# led-matrix-cape.net
KiCad netlist of a schematic drawn in EAGLE
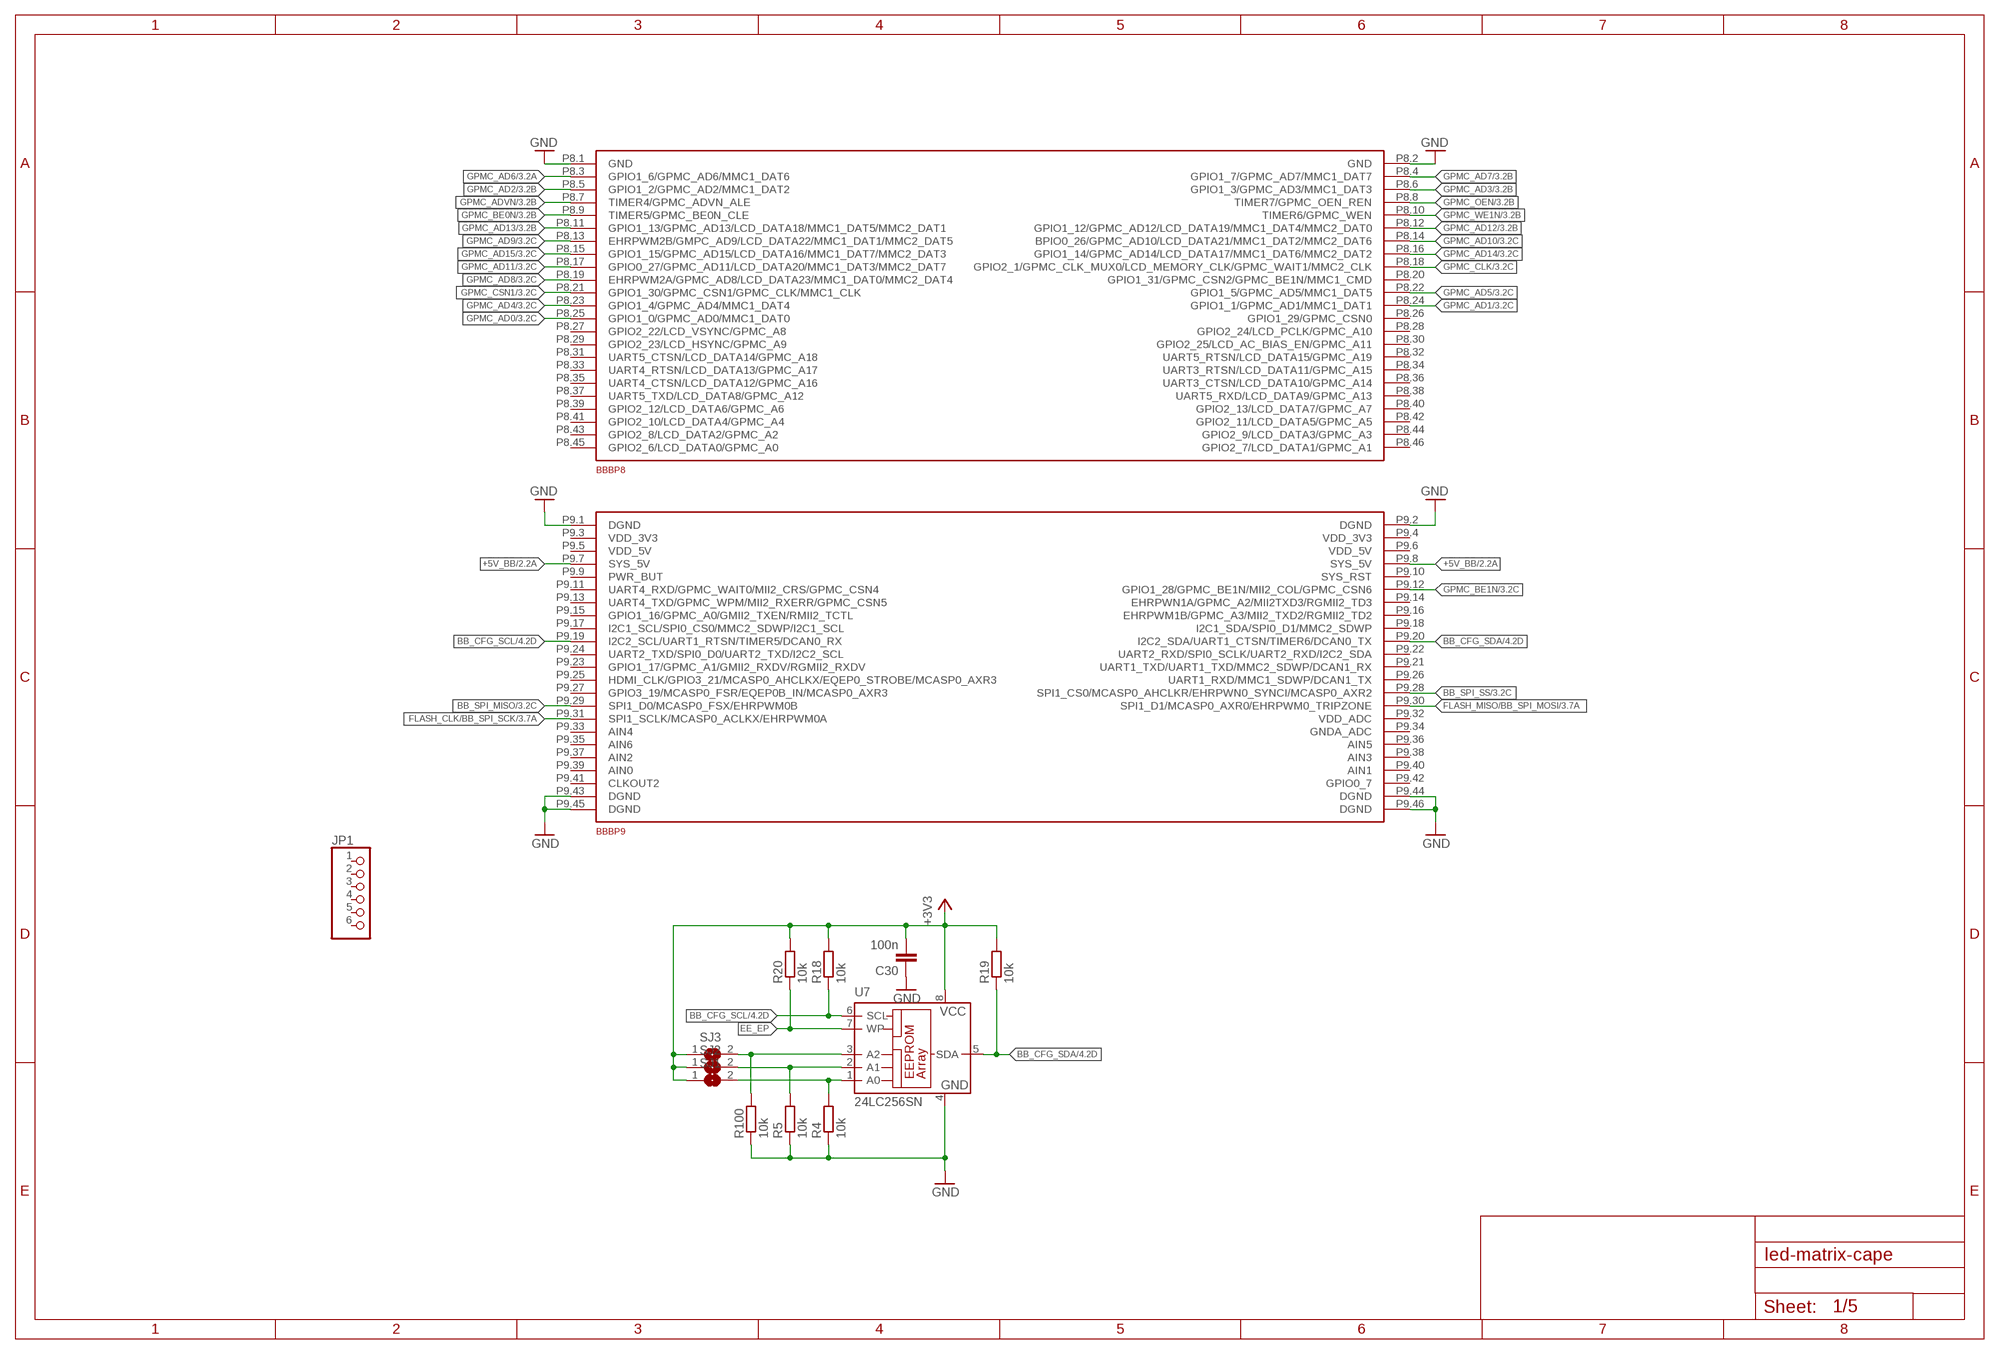
[diagram p0: schematic, sheet 1]
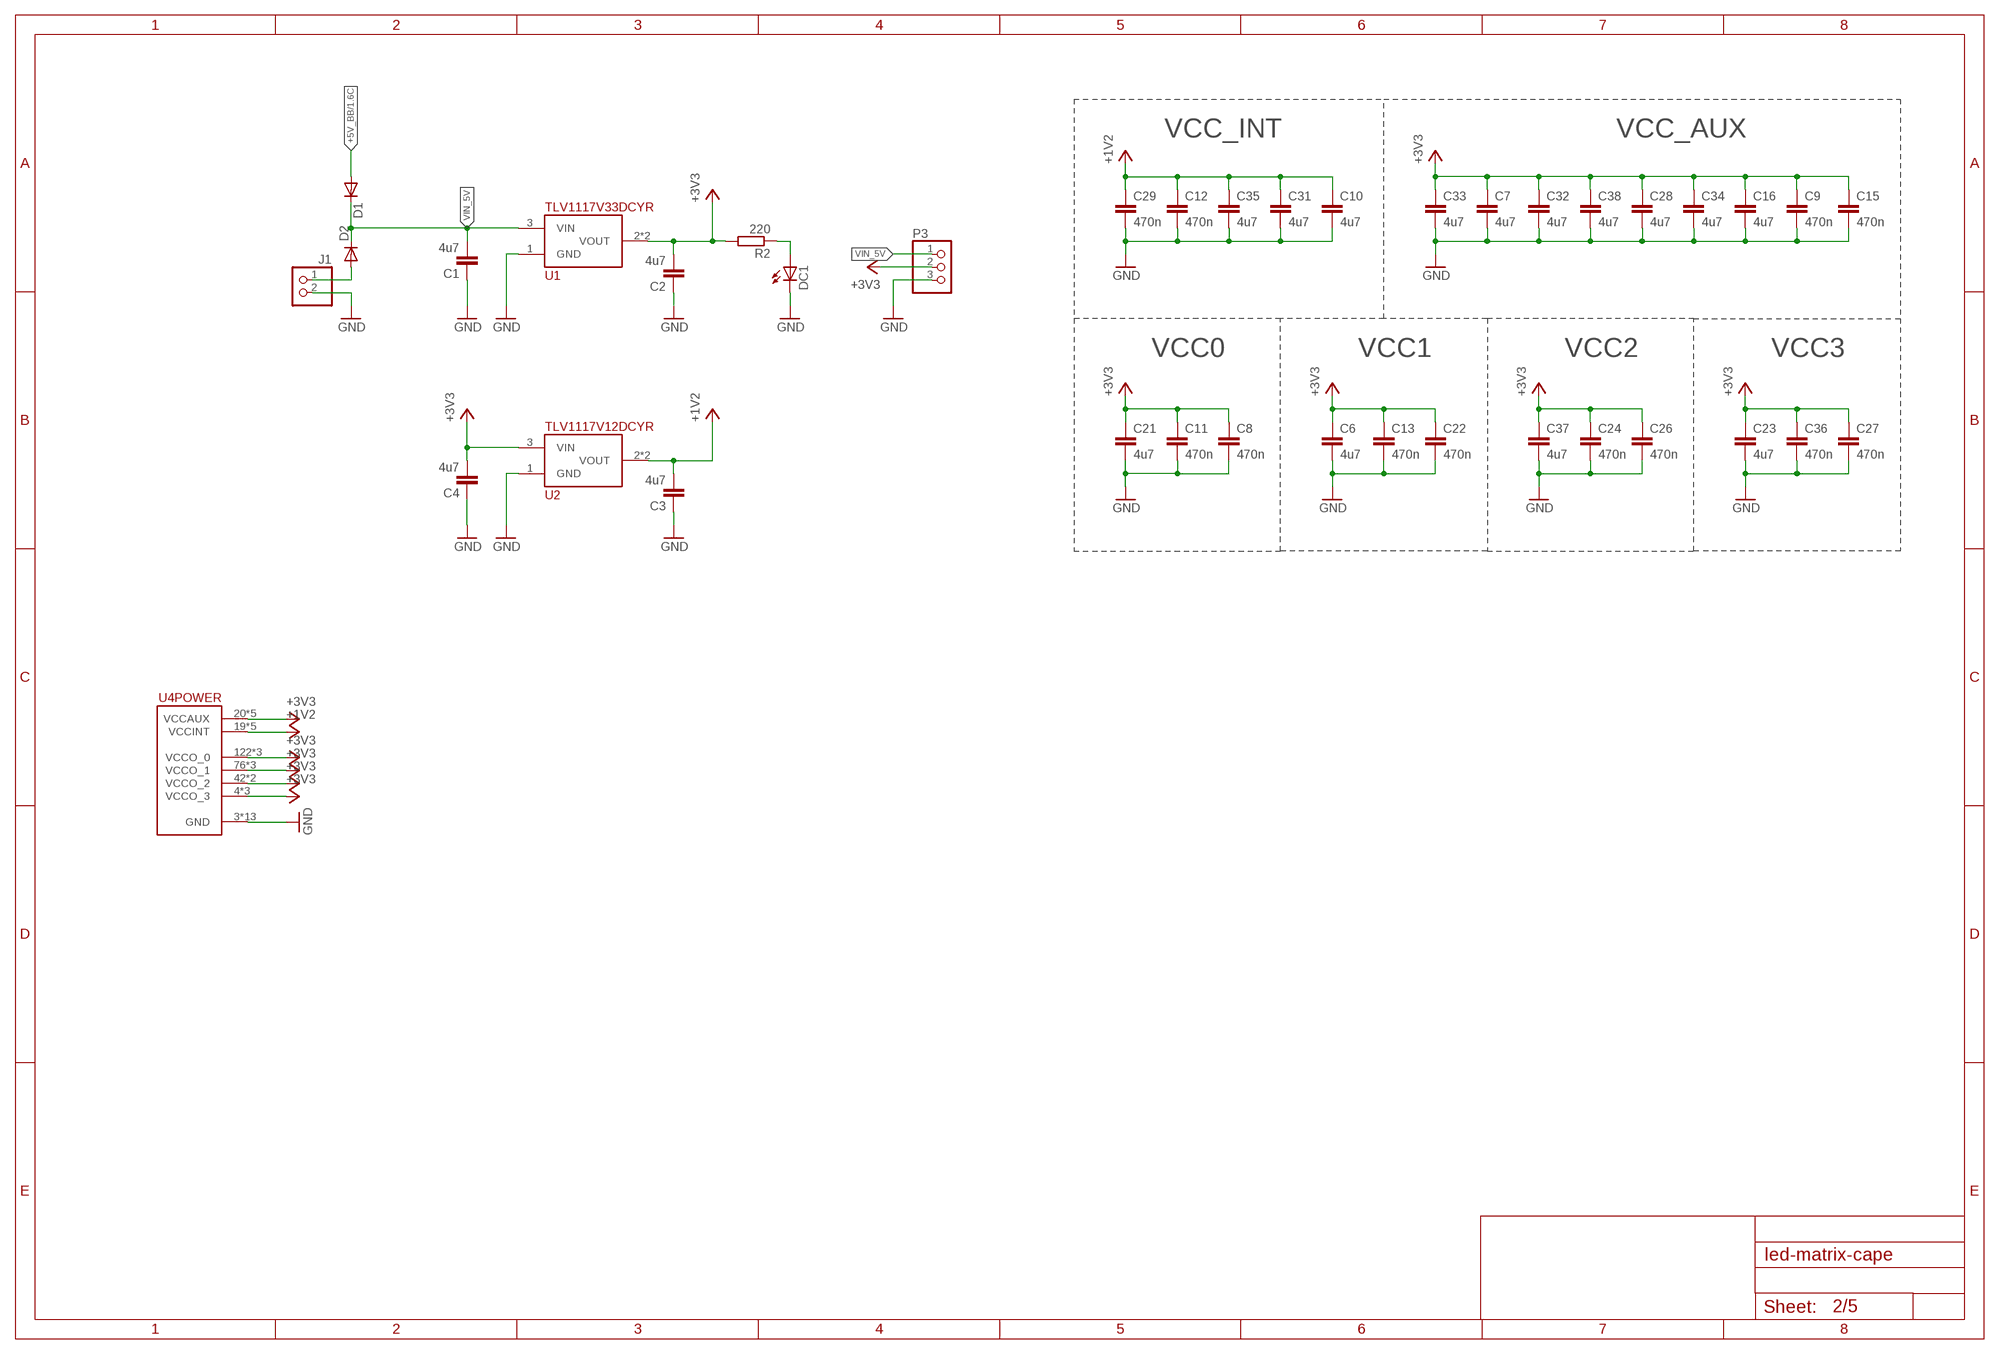
[diagram p1: schematic, sheet 2]
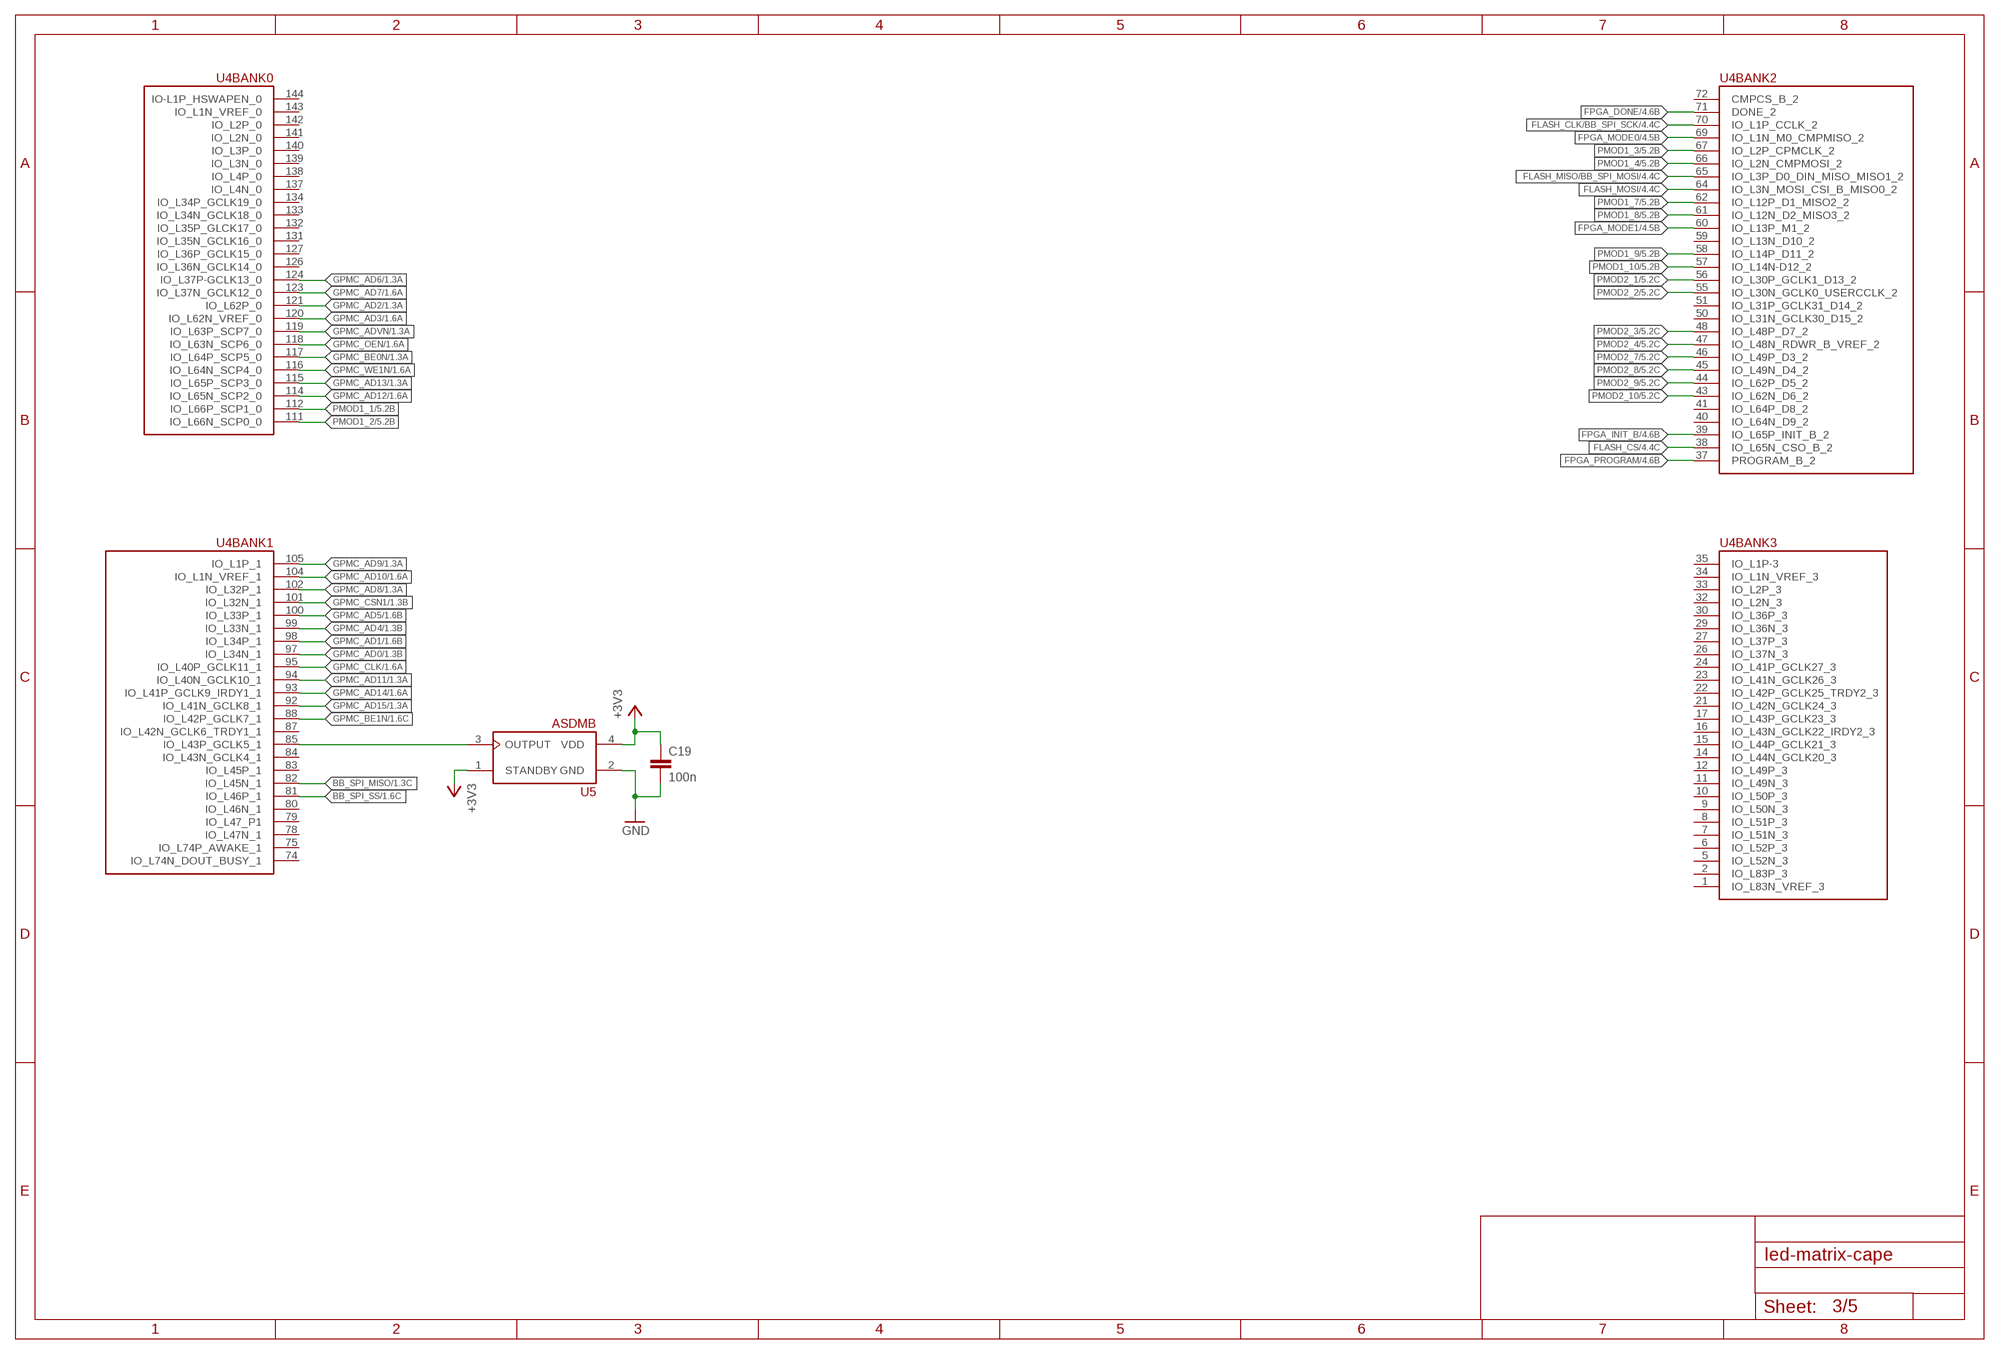
[diagram p2: schematic, sheet 3]
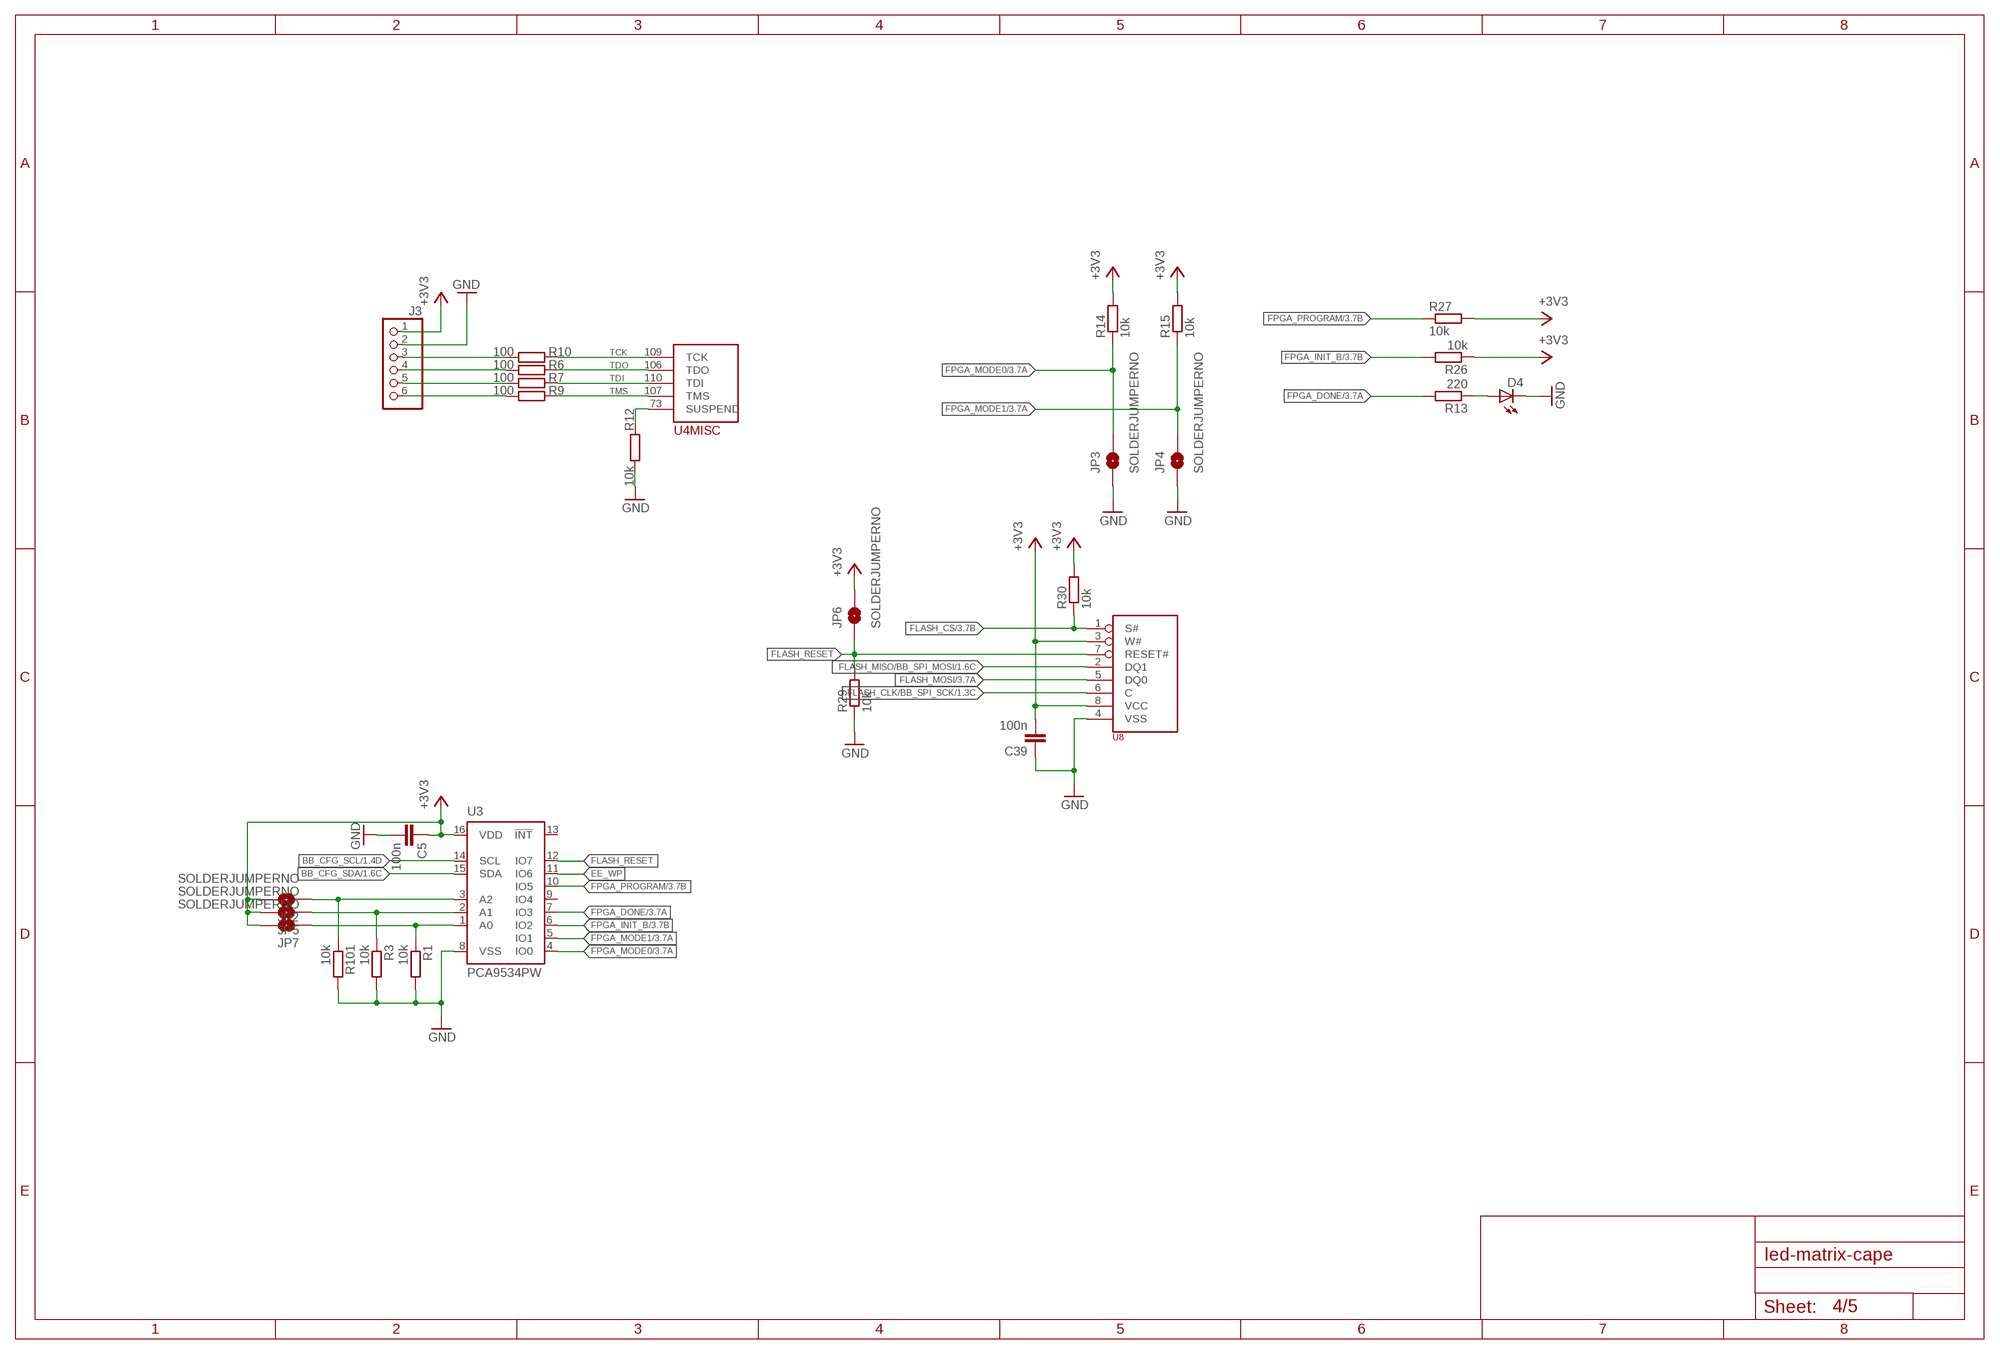
[diagram p3: schematic, sheet 4]
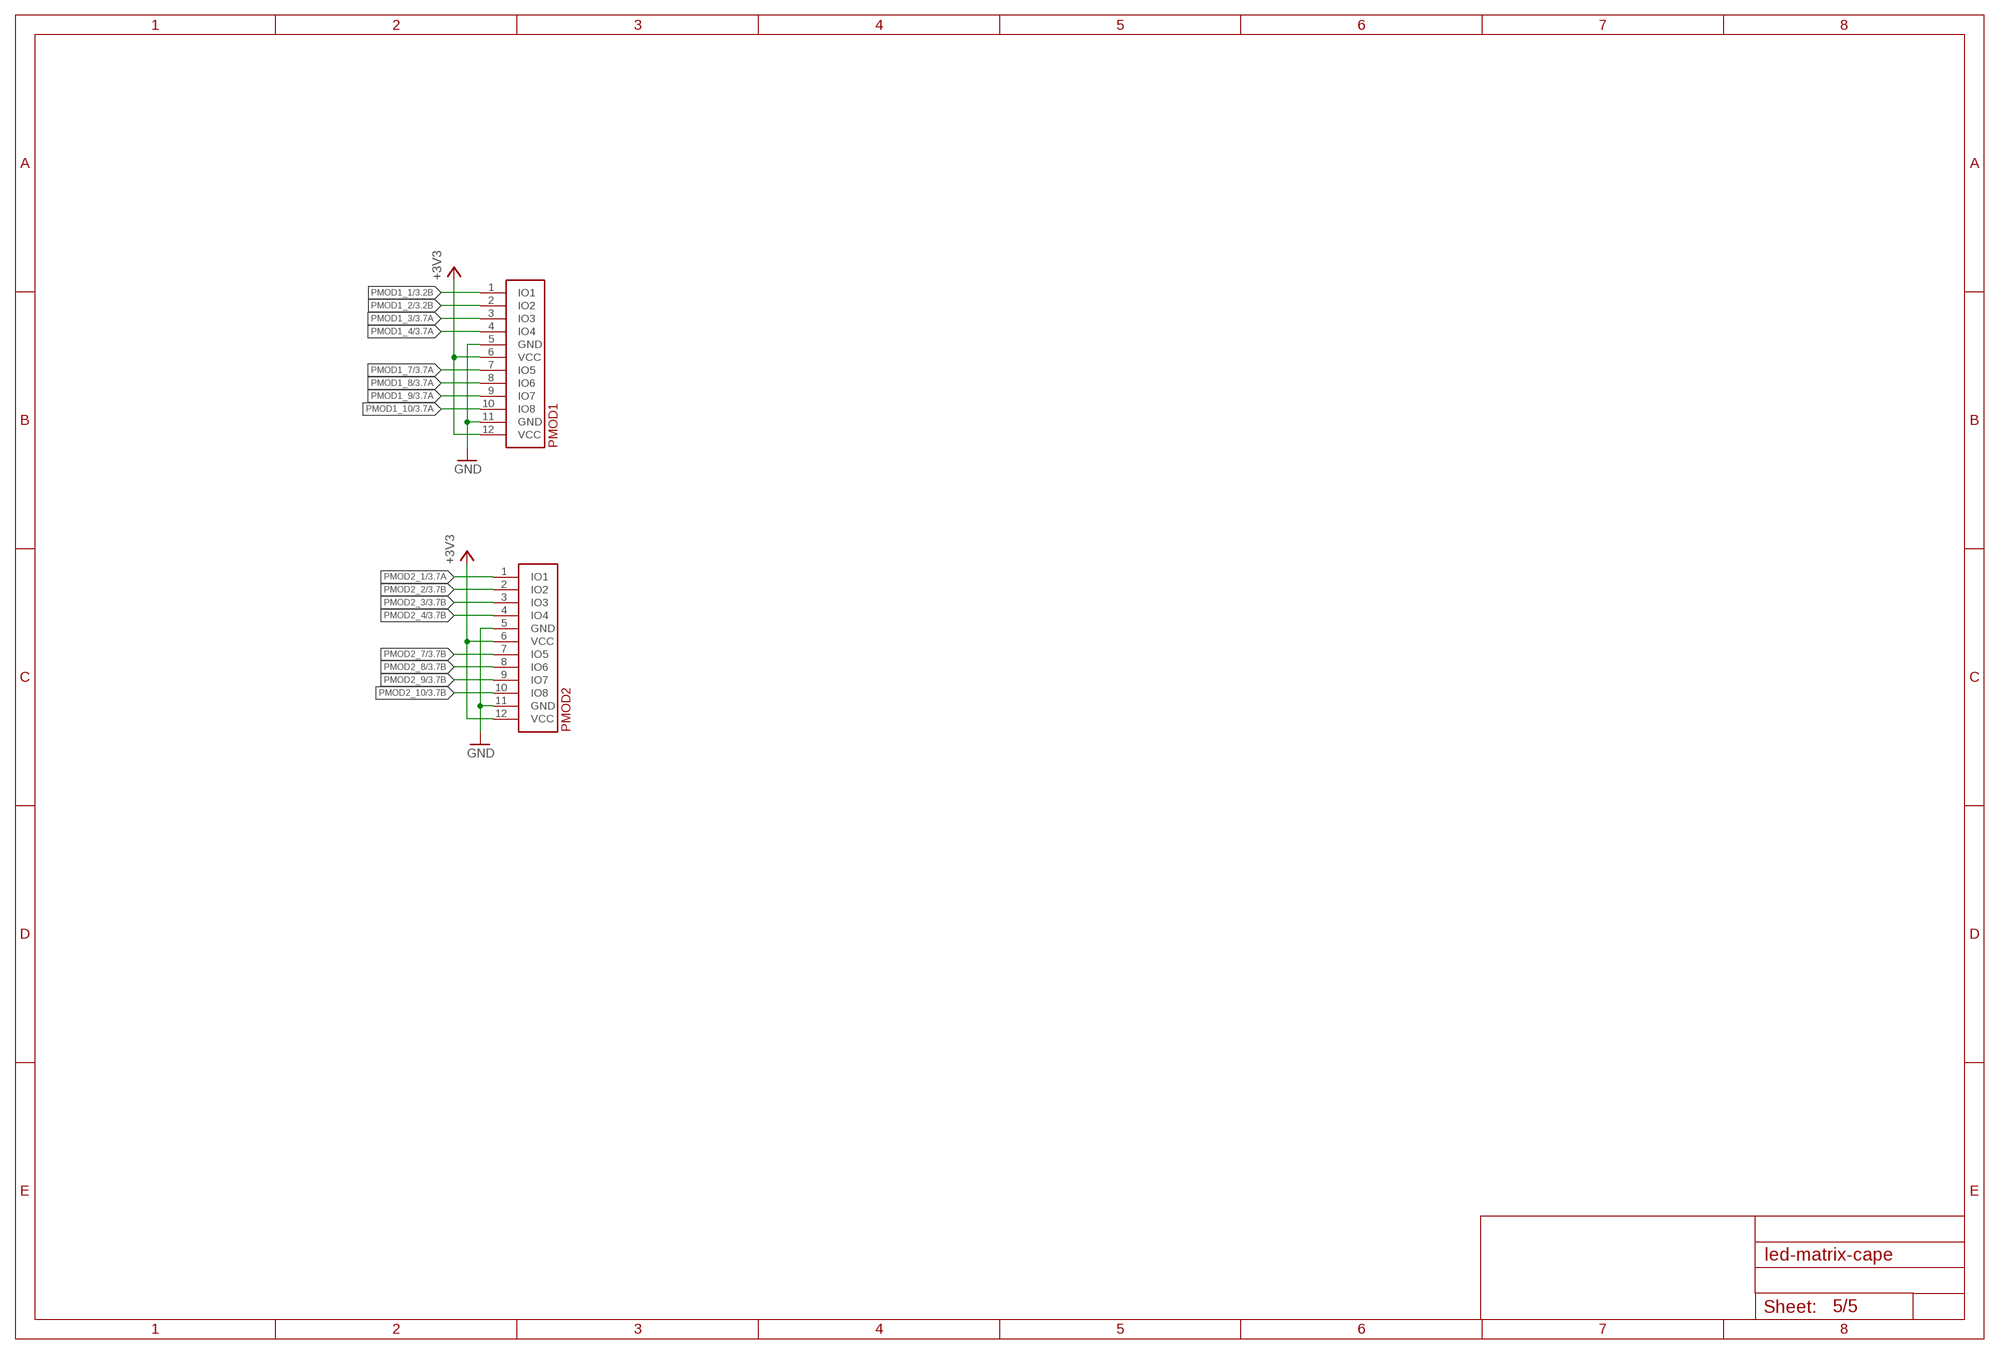
[diagram p4: schematic, sheet 5]

(export (version "E")
  (design (tool "Eeschema 10.0.6"))
  (components
    (comp (ref "C1")
      (value "4u7")
      (footprint "eagle-import:C0603")
      (libsource (lib "eagle-import") (part "C-EUC0603"))
    )
    (comp (ref "C2")
      (value "4u7")
      (footprint "eagle-import:C0603")
      (libsource (lib "eagle-import") (part "C-EUC0603"))
    )
    (comp (ref "C3")
      (value "4u7")
      (footprint "eagle-import:C0603")
      (libsource (lib "eagle-import") (part "C-EUC0603"))
    )
    (comp (ref "C4")
      (value "4u7")
      (footprint "eagle-import:C0603")
      (libsource (lib "eagle-import") (part "C-EUC0603"))
    )
    (comp (ref "C6")
      (value "4u7")
      (footprint "eagle-import:C0603")
      (libsource (lib "eagle-import") (part "C-EUC0603"))
    )
    (comp (ref "C7")
      (value "4u7")
      (footprint "eagle-import:C0603")
      (libsource (lib "eagle-import") (part "C-EUC0603"))
    )
    (comp (ref "C8")
      (value "470n")
      (footprint "eagle-import:C0603")
      (libsource (lib "eagle-import") (part "C-EUC0603"))
    )
    (comp (ref "C9")
      (value "470n")
      (footprint "eagle-import:C0603")
      (libsource (lib "eagle-import") (part "C-EUC0603"))
    )
    (comp (ref "C10")
      (value "4u7")
      (footprint "eagle-import:C0603")
      (libsource (lib "eagle-import") (part "C-EUC0603"))
    )
    (comp (ref "C11")
      (value "470n")
      (footprint "eagle-import:C0603")
      (libsource (lib "eagle-import") (part "C-EUC0603"))
    )
    (comp (ref "C12")
      (value "470n")
      (footprint "eagle-import:C0603")
      (libsource (lib "eagle-import") (part "C-EUC0603"))
    )
    (comp (ref "C13")
      (value "470n")
      (footprint "eagle-import:C0603")
      (libsource (lib "eagle-import") (part "C-EUC0603"))
    )
    (comp (ref "C15")
      (value "470n")
      (footprint "eagle-import:C0603")
      (libsource (lib "eagle-import") (part "C-EUC0603"))
    )
    (comp (ref "C16")
      (value "4u7")
      (footprint "eagle-import:C0603")
      (libsource (lib "eagle-import") (part "C-EUC0603"))
    )
    (comp (ref "C21")
      (value "4u7")
      (footprint "eagle-import:C0603")
      (libsource (lib "eagle-import") (part "C-EUC0603"))
    )
    (comp (ref "C22")
      (value "470n")
      (footprint "eagle-import:C0603")
      (libsource (lib "eagle-import") (part "C-EUC0603"))
    )
    (comp (ref "C23")
      (value "4u7")
      (footprint "eagle-import:C0603")
      (libsource (lib "eagle-import") (part "C-EUC0603"))
    )
    (comp (ref "C24")
      (value "470n")
      (footprint "eagle-import:C0603")
      (libsource (lib "eagle-import") (part "C-EUC0603"))
    )
    (comp (ref "C26")
      (value "470n")
      (footprint "eagle-import:C0603")
      (libsource (lib "eagle-import") (part "C-EUC0603"))
    )
    (comp (ref "C27")
      (value "470n")
      (footprint "eagle-import:C0603")
      (libsource (lib "eagle-import") (part "C-EUC0603"))
    )
    (comp (ref "C28")
      (value "4u7")
      (footprint "eagle-import:C0603")
      (libsource (lib "eagle-import") (part "C-EUC0603"))
    )
    (comp (ref "C29")
      (value "470n")
      (footprint "eagle-import:C0603")
      (libsource (lib "eagle-import") (part "C-EUC0603"))
    )
    (comp (ref "C31")
      (value "4u7")
      (footprint "eagle-import:C0603")
      (libsource (lib "eagle-import") (part "C-EUC0603"))
    )
    (comp (ref "C32")
      (value "4u7")
      (footprint "eagle-import:C0603")
      (libsource (lib "eagle-import") (part "C-EUC0603"))
    )
    (comp (ref "C33")
      (value "4u7")
      (footprint "eagle-import:C0603")
      (libsource (lib "eagle-import") (part "C-EUC0603"))
    )
    (comp (ref "C34")
      (value "4u7")
      (footprint "eagle-import:C0603")
      (libsource (lib "eagle-import") (part "C-EUC0603"))
    )
    (comp (ref "C35")
      (value "4u7")
      (footprint "eagle-import:C0603")
      (libsource (lib "eagle-import") (part "C-EUC0603"))
    )
    (comp (ref "C36")
      (value "470n")
      (footprint "eagle-import:C0603")
      (libsource (lib "eagle-import") (part "C-EUC0603"))
    )
    (comp (ref "C37")
      (value "4u7")
      (footprint "eagle-import:C0603")
      (libsource (lib "eagle-import") (part "C-EUC0603"))
    )
    (comp (ref "C38")
      (value "4u7")
      (footprint "eagle-import:C0603")
      (libsource (lib "eagle-import") (part "C-EUC0603"))
    )
    (comp (ref "D1")
      (value "DIODE-SOD123")
      (footprint "eagle-import:SOD123")
      (libsource (lib "eagle-import") (part "DIODE-SOD123"))
    )
    (comp (ref "D2")
      (value "DIODE-SOD123")
      (footprint "eagle-import:SOD123")
      (libsource (lib "eagle-import") (part "DIODE-SOD123"))
    )
    (comp (ref "DC1")
      (value "LEDCHIP-LED0805")
      (footprint "eagle-import:CHIP-LED0805")
      (libsource (lib "eagle-import") (part "LEDCHIP-LED0805"))
    )
    (comp (ref "J1")
      (value "PINHD-1X2")
      (footprint "eagle-import:1X02")
      (libsource (lib "eagle-import") (part "PINHD-1X2"))
    )
    (comp (ref "P3")
      (value "PINHD-1X3")
      (footprint "eagle-import:1X03")
      (libsource (lib "eagle-import") (part "PINHD-1X3"))
    )
    (comp (ref "R2")
      (value "220")
      (footprint "eagle-import:R0805")
      (libsource (lib "eagle-import") (part "R-EU_R0805"))
    )
    (comp (ref "U1")
      (value "TLV1117V33DCYR")
      (footprint "eagle-import:SOT223")
      (libsource (lib "eagle-import") (part "TLV1117V"))
    )
    (comp (ref "U2")
      (value "TLV1117V12DCYR")
      (footprint "eagle-import:SOT223")
      (libsource (lib "eagle-import") (part "TLV1117V"))
    )
    (comp (ref "U4")
      (value "XC6SLX9-2TQG144C")
      (footprint "eagle-import:TQFP144")
      (libsource (lib "eagle-import") (part "XC6SLX9-2TQG144C"))
    )
    (comp (ref "C5")
      (value "100n")
      (footprint "eagle-import:C0603")
      (libsource (lib "eagle-import") (part "C-EUC0603"))
    )
    (comp (ref "C39")
      (value "100n")
      (footprint "eagle-import:C0603")
      (libsource (lib "eagle-import") (part "C-EUC0603"))
    )
    (comp (ref "D4")
      (value "LEDCHIP-LED0805")
      (footprint "eagle-import:CHIP-LED0805")
      (libsource (lib "eagle-import") (part "LEDCHIP-LED0805"))
    )
    (comp (ref "J3")
      (value "PINHD-1X6")
      (footprint "eagle-import:1X06")
      (libsource (lib "eagle-import") (part "PINHD-1X6"))
    )
    (comp (ref "JP2")
      (value "SOLDERJUMPERNO")
      (footprint "eagle-import:SJ_2S-NO")
      (libsource (lib "eagle-import") (part "SOLDERJUMPERNO"))
    )
    (comp (ref "JP3")
      (value "SOLDERJUMPERNO")
      (footprint "eagle-import:SJ_2S-NO")
      (libsource (lib "eagle-import") (part "SOLDERJUMPERNO"))
    )
    (comp (ref "JP4")
      (value "SOLDERJUMPERNO")
      (footprint "eagle-import:SJ_2S-NO")
      (libsource (lib "eagle-import") (part "SOLDERJUMPERNO"))
    )
    (comp (ref "JP5")
      (value "SOLDERJUMPERNO")
      (footprint "eagle-import:SJ_2S-NO")
      (libsource (lib "eagle-import") (part "SOLDERJUMPERNO"))
    )
    (comp (ref "JP6")
      (value "SOLDERJUMPERNO")
      (footprint "eagle-import:SJ_2S-NO")
      (libsource (lib "eagle-import") (part "SOLDERJUMPERNO"))
    )
    (comp (ref "JP7")
      (value "SOLDERJUMPERNO")
      (footprint "eagle-import:SJ_2S-NO")
      (libsource (lib "eagle-import") (part "SOLDERJUMPERNO"))
    )
    (comp (ref "R1")
      (value "10k")
      (footprint "eagle-import:R0603")
      (libsource (lib "eagle-import") (part "R-EU_R0603"))
    )
    (comp (ref "R3")
      (value "10k")
      (footprint "eagle-import:R0603")
      (libsource (lib "eagle-import") (part "R-EU_R0603"))
    )
    (comp (ref "R6")
      (value "100")
      (footprint "eagle-import:R0603")
      (libsource (lib "eagle-import") (part "R-EU_R0603"))
    )
    (comp (ref "R7")
      (value "100")
      (footprint "eagle-import:R0603")
      (libsource (lib "eagle-import") (part "R-EU_R0603"))
    )
    (comp (ref "R9")
      (value "100")
      (footprint "eagle-import:R0603")
      (libsource (lib "eagle-import") (part "R-EU_R0603"))
    )
    (comp (ref "R10")
      (value "100")
      (footprint "eagle-import:R0603")
      (libsource (lib "eagle-import") (part "R-EU_R0603"))
    )
    (comp (ref "R12")
      (value "10k")
      (footprint "eagle-import:R0603")
      (libsource (lib "eagle-import") (part "R-EU_R0603"))
    )
    (comp (ref "R13")
      (value "220")
      (footprint "eagle-import:R0603")
      (libsource (lib "eagle-import") (part "R-EU_R0603"))
    )
    (comp (ref "R14")
      (value "10k")
      (footprint "eagle-import:R0603")
      (libsource (lib "eagle-import") (part "R-EU_R0603"))
    )
    (comp (ref "R15")
      (value "10k")
      (footprint "eagle-import:R0603")
      (libsource (lib "eagle-import") (part "R-EU_R0603"))
    )
    (comp (ref "R26")
      (value "10k")
      (footprint "eagle-import:R0603")
      (libsource (lib "eagle-import") (part "R-EU_R0603"))
    )
    (comp (ref "R27")
      (value "10k")
      (footprint "eagle-import:R0603")
      (libsource (lib "eagle-import") (part "R-EU_R0603"))
    )
    (comp (ref "R29")
      (value "10k")
      (footprint "eagle-import:R0805")
      (libsource (lib "eagle-import") (part "R-EU_R0805"))
    )
    (comp (ref "R30")
      (value "10k")
      (footprint "eagle-import:R0603")
      (libsource (lib "eagle-import") (part "R-EU_R0603"))
    )
    (comp (ref "R101")
      (value "10k")
      (footprint "eagle-import:R0603")
      (libsource (lib "eagle-import") (part "R-EU_R0603"))
    )
    (comp (ref "U3")
      (value "PCA9534PW")
      (footprint "eagle-import:TSSOP16")
      (libsource (lib "eagle-import") (part "PCA9534PW"))
    )
    (comp (ref "U8")
      (value "M25PE16")
      (footprint "eagle-import:SO8")
      (libsource (lib "eagle-import") (part "M25PE16"))
    )
    (comp (ref "BBB")
      (value "BEAGLEBONE_CAPE_CONNECTORS")
      (footprint "eagle-import:BEAGLEBONE_CAPE")
      (libsource (lib "eagle-import") (part "BEAGLEBONE_CAPE_CONNECTORS"))
    )
    (comp (ref "C30")
      (value "100n")
      (footprint "eagle-import:C0603")
      (libsource (lib "eagle-import") (part "C-EUC0603"))
    )
    (comp (ref "JP1")
      (value "PINHD-1X6")
      (footprint "eagle-import:1X06")
      (libsource (lib "eagle-import") (part "PINHD-1X6"))
    )
    (comp (ref "R4")
      (value "10k")
      (footprint "eagle-import:R0603")
      (libsource (lib "eagle-import") (part "R-EU_R0603"))
    )
    (comp (ref "R5")
      (value "10k")
      (footprint "eagle-import:R0603")
      (libsource (lib "eagle-import") (part "R-EU_R0603"))
    )
    (comp (ref "R18")
      (value "10k")
      (footprint "eagle-import:R0603")
      (libsource (lib "eagle-import") (part "R-EU_R0603"))
    )
    (comp (ref "R19")
      (value "10k")
      (footprint "eagle-import:R0603")
      (libsource (lib "eagle-import") (part "R-EU_R0603"))
    )
    (comp (ref "R20")
      (value "10k")
      (footprint "eagle-import:R0603")
      (libsource (lib "eagle-import") (part "R-EU_R0603"))
    )
    (comp (ref "R100")
      (value "10k")
      (footprint "eagle-import:R0603")
      (libsource (lib "eagle-import") (part "R-EU_R0603"))
    )
    (comp (ref "SJ1") (value "SJ") (footprint "eagle-import:SJ") (libsource (lib "eagle-import") (part "SJ")))
    (comp (ref "SJ2") (value "SJ") (footprint "eagle-import:SJ") (libsource (lib "eagle-import") (part "SJ")))
    (comp (ref "SJ3") (value "SJ") (footprint "eagle-import:SJ") (libsource (lib "eagle-import") (part "SJ")))
    (comp (ref "U7")
      (value "24LC256SN")
      (footprint "eagle-import:SO-08")
      (fields (field (name "MF") "MICROCHIP") (field (name "MPN") "24LC256-I/SN"))
      (libsource (lib "eagle-import") (part "24SNLC256"))
    )
    (comp (ref "C19")
      (value "100n")
      (footprint "eagle-import:C0603")
      (libsource (lib "eagle-import") (part "C-EUC0603"))
    )
    (comp (ref "U5")
      (value "ASDMB")
      (footprint "eagle-import:ASDMB")
      (libsource (lib "eagle-import") (part "ASDMB"))
    )
    (comp (ref "PMOD1")
      (value "PMOD_2_HOST")
      (footprint "eagle-import:PMOD_2_HOST")
      (libsource (lib "eagle-import") (part "PMOD_2_HOST"))
    )
    (comp (ref "PMOD2")
      (value "PMOD_2_HOST")
      (footprint "eagle-import:PMOD_2_HOST")
      (libsource (lib "eagle-import") (part "PMOD_2_HOST"))
    )
  )
  (nets
    (net (code "1") (name "+1V2") (class "Default")
      (node (ref "C10") (pin "1") (pinfunction "1_1") (pintype "passive"))
      (node (ref "C12") (pin "1") (pinfunction "1_1") (pintype "passive"))
      (node (ref "C29") (pin "1") (pinfunction "1_1") (pintype "passive"))
      (node (ref "C3") (pin "2") (pinfunction "2_2") (pintype "passive"))
      (node (ref "C31") (pin "1") (pinfunction "1_1") (pintype "passive"))
      (node (ref "C35") (pin "1") (pinfunction "1_1") (pintype "passive"))
      (node (ref "U2") (pin "2") (pinfunction "VOUT_2") (pintype "passive"))
      (node (ref "U2") (pin "4") (pinfunction "VOUT_4") (pintype "passive"))
      (node (ref "U4") (pin "128") (pinfunction "VCCINT_128") (pintype "power_in"))
      (node (ref "U4") (pin "19") (pinfunction "VCCINT_19") (pintype "power_in"))
      (node (ref "U4") (pin "28") (pinfunction "VCCINT_28") (pintype "power_in"))
      (node (ref "U4") (pin "52") (pinfunction "VCCINT_52") (pintype "power_in"))
      (node (ref "U4") (pin "89") (pinfunction "VCCINT_89") (pintype "power_in"))
    )
    (net (code "2") (name "+3V3") (class "Default")
      (node (ref "C11") (pin "1") (pinfunction "1_1") (pintype "passive"))
      (node (ref "C13") (pin "1") (pinfunction "1_1") (pintype "passive"))
      (node (ref "C15") (pin "1") (pinfunction "1_1") (pintype "passive"))
      (node (ref "C16") (pin "1") (pinfunction "1_1") (pintype "passive"))
      (node (ref "C19") (pin "1") (pinfunction "1_1") (pintype "passive"))
      (node (ref "C2") (pin "2") (pinfunction "2_2") (pintype "passive"))
      (node (ref "C21") (pin "1") (pinfunction "1_1") (pintype "passive"))
      (node (ref "C22") (pin "1") (pinfunction "1_1") (pintype "passive"))
      (node (ref "C23") (pin "1") (pinfunction "1_1") (pintype "passive"))
      (node (ref "C24") (pin "1") (pinfunction "1_1") (pintype "passive"))
      (node (ref "C26") (pin "1") (pinfunction "1_1") (pintype "passive"))
      (node (ref "C27") (pin "1") (pinfunction "1_1") (pintype "passive"))
      (node (ref "C28") (pin "1") (pinfunction "1_1") (pintype "passive"))
      (node (ref "C30") (pin "2") (pinfunction "2_2") (pintype "passive"))
      (node (ref "C32") (pin "1") (pinfunction "1_1") (pintype "passive"))
      (node (ref "C33") (pin "1") (pinfunction "1_1") (pintype "passive"))
      (node (ref "C34") (pin "1") (pinfunction "1_1") (pintype "passive"))
      (node (ref "C36") (pin "1") (pinfunction "1_1") (pintype "passive"))
      (node (ref "C37") (pin "1") (pinfunction "1_1") (pintype "passive"))
      (node (ref "C38") (pin "1") (pinfunction "1_1") (pintype "passive"))
      (node (ref "C39") (pin "2") (pinfunction "2_2") (pintype "passive"))
      (node (ref "C4") (pin "2") (pinfunction "2_2") (pintype "passive"))
      (node (ref "C5") (pin "1") (pinfunction "1_1") (pintype "passive"))
      (node (ref "C6") (pin "1") (pinfunction "1_1") (pintype "passive"))
      (node (ref "C7") (pin "1") (pinfunction "1_1") (pintype "passive"))
      (node (ref "C8") (pin "1") (pinfunction "1_1") (pintype "passive"))
      (node (ref "C9") (pin "1") (pinfunction "1_1") (pintype "passive"))
      (node (ref "J3") (pin "1") (pinfunction "1_1") (pintype "passive"))
      (node (ref "JP2") (pin "2") (pinfunction "2_2") (pintype "passive"))
      (node (ref "JP5") (pin "2") (pinfunction "2_2") (pintype "passive"))
      (node (ref "JP6") (pin "2") (pinfunction "2_2") (pintype "passive"))
      (node (ref "JP7") (pin "2") (pinfunction "2_2") (pintype "passive"))
      (node (ref "P3") (pin "2") (pinfunction "2_2") (pintype "passive"))
      (node (ref "PMOD1") (pin "12") (pinfunction "VCC_12") (pintype "bidirectional"))
      (node (ref "PMOD1") (pin "6") (pinfunction "VCC_6") (pintype "power_in"))
      (node (ref "PMOD2") (pin "12") (pinfunction "VCC_12") (pintype "bidirectional"))
      (node (ref "PMOD2") (pin "6") (pinfunction "VCC_6") (pintype "power_in"))
      (node (ref "R14") (pin "2") (pinfunction "2_2") (pintype "passive"))
      (node (ref "R15") (pin "2") (pinfunction "2_2") (pintype "passive"))
      (node (ref "R18") (pin "2") (pinfunction "2_2") (pintype "passive"))
      (node (ref "R19") (pin "2") (pinfunction "2_2") (pintype "passive"))
      (node (ref "R2") (pin "2") (pinfunction "2_2") (pintype "passive"))
      (node (ref "R20") (pin "2") (pinfunction "2_2") (pintype "passive"))
      (node (ref "R26") (pin "1") (pinfunction "1_1") (pintype "passive"))
      (node (ref "R27") (pin "2") (pinfunction "2_2") (pintype "passive"))
      (node (ref "R30") (pin "2") (pinfunction "2_2") (pintype "passive"))
      (node (ref "SJ1") (pin "1") (pinfunction "1_1") (pintype "passive"))
      (node (ref "SJ2") (pin "1") (pinfunction "1_1") (pintype "passive"))
      (node (ref "SJ3") (pin "1") (pinfunction "1_1") (pintype "passive"))
      (node (ref "U1") (pin "2") (pinfunction "VOUT_2") (pintype "passive"))
      (node (ref "U1") (pin "4") (pinfunction "VOUT_4") (pintype "passive"))
      (node (ref "U2") (pin "3") (pinfunction "VIN_3") (pintype "power_in"))
      (node (ref "U3") (pin "16") (pinfunction "VDD_16") (pintype "power_in"))
      (node (ref "U4") (pin "103") (pinfunction "VCCO_1_103") (pintype "power_in"))
      (node (ref "U4") (pin "122") (pinfunction "VCCO_0_122") (pintype "power_in"))
      (node (ref "U4") (pin "125") (pinfunction "VCCO_0_125") (pintype "power_in"))
      (node (ref "U4") (pin "129") (pinfunction "VCCAUX_129") (pintype "power_in"))
      (node (ref "U4") (pin "135") (pinfunction "VCCO_0_135") (pintype "power_in"))
      (node (ref "U4") (pin "18") (pinfunction "VCCO_3_18") (pintype "power_in"))
      (node (ref "U4") (pin "20") (pinfunction "VCCAUX_20") (pintype "power_in"))
      (node (ref "U4") (pin "31") (pinfunction "VCCO_3_31") (pintype "power_in"))
      (node (ref "U4") (pin "36") (pinfunction "VCCAUX_36") (pintype "power_in"))
      (node (ref "U4") (pin "4") (pinfunction "VCCO_3_4") (pintype "power_in"))
      (node (ref "U4") (pin "42") (pinfunction "VCCO_2_42") (pintype "power_in"))
      (node (ref "U4") (pin "53") (pinfunction "VCCAUX_53") (pintype "power_in"))
      (node (ref "U4") (pin "63") (pinfunction "VCCO_2_63") (pintype "power_in"))
      (node (ref "U4") (pin "76") (pinfunction "VCCO_1_76") (pintype "power_in"))
      (node (ref "U4") (pin "86") (pinfunction "VCCO_1_86") (pintype "power_in"))
      (node (ref "U4") (pin "90") (pinfunction "VCCAUX_90") (pintype "power_in"))
      (node (ref "U5") (pin "1") (pinfunction "STANDBY_1") (pintype "input"))
      (node (ref "U5") (pin "4") (pinfunction "VDD_4") (pintype "power_in"))
      (node (ref "U7") (pin "8") (pinfunction "VCC_8") (pintype "power_in"))
      (node (ref "U8") (pin "3") (pinfunction "W#_3") (pintype "input"))
      (node (ref "U8") (pin "8") (pinfunction "VCC_8") (pintype "passive"))
    )
    (net (code "3") (name "+5V_BB") (class "Default")
      (node (ref "BBB") (pin "P9.7") (pinfunction "SYS_5V_P9.7") (pintype "bidirectional"))
      (node (ref "BBB") (pin "P9.8") (pinfunction "SYS_5V_P9.8") (pintype "bidirectional"))
      (node (ref "D1") (pin "A") (pinfunction "A_A") (pintype "passive"))
    )
    (net (code "4") (name "BB_CFG_SCL") (class "Default")
      (node (ref "BBB") (pin "P9.19") (pinfunction "I2C2_SCL/UART1_RTSN/TIMER5/DCAN0_RX_P9.19") (pintype "bidirectional"))
      (node (ref "R18") (pin "1") (pinfunction "1_1") (pintype "passive"))
      (node (ref "U3") (pin "14") (pinfunction "SCL_14") (pintype "input"))
      (node (ref "U7") (pin "6") (pinfunction "SCL_6") (pintype "input"))
    )
    (net (code "5") (name "BB_CFG_SDA") (class "Default")
      (node (ref "BBB") (pin "P9.20") (pinfunction "I2C2_SDA/UART1_CTSN/TIMER6/DCAN0_TX_P9.20") (pintype "bidirectional"))
      (node (ref "R19") (pin "1") (pinfunction "1_1") (pintype "passive"))
      (node (ref "U3") (pin "15") (pinfunction "SDA_15") (pintype "bidirectional"))
      (node (ref "U7") (pin "5") (pinfunction "SDA_5") (pintype "bidirectional"))
    )
    (net (code "6") (name "BB_SPI_MISO") (class "Default")
      (node (ref "BBB") (pin "P9.29") (pinfunction "SPI1_D0/MCASP0_FSX/EHRPWM0B_P9.29") (pintype "bidirectional"))
      (node (ref "U4") (pin "82") (pinfunction "IO_L45N_1_82") (pintype "bidirectional"))
    )
    (net (code "7") (name "BB_SPI_SS") (class "Default")
      (node (ref "BBB") (pin "P9.28") (pinfunction "SPI1_CS0/MCASP0_AHCLKR/EHRPWN0_SYNCI/MCASP0_AXR2_P9.28") (pintype "bidirectional"))
      (node (ref "U4") (pin "81") (pinfunction "IO_L46P_1_81") (pintype "bidirectional"))
    )
    (net (code "8") (name "EE_EP") (class "Default")
      (node (ref "R20") (pin "1") (pinfunction "1_1") (pintype "passive"))
      (node (ref "U7") (pin "7") (pinfunction "WP_7") (pintype "input"))
    )
    (net (code "9") (name "EE_WP") (class "Default")
      (node (ref "U3") (pin "11") (pinfunction "IO6_11") (pintype "bidirectional"))
    )
    (net (code "10") (name "FLASH_CLK{slash}BB_SPI_SCK") (class "Default")
      (node (ref "BBB") (pin "P9.31") (pinfunction "SPI1_SCLK/MCASP0_ACLKX/EHRPWM0A_P9.31") (pintype "bidirectional"))
      (node (ref "U4") (pin "70") (pinfunction "IO_L1P_CCLK_2_70") (pintype "bidirectional"))
      (node (ref "U8") (pin "6") (pinfunction "C_6") (pintype "input"))
    )
    (net (code "11") (name "FLASH_CS") (class "Default")
      (node (ref "R30") (pin "1") (pinfunction "1_1") (pintype "passive"))
      (node (ref "U4") (pin "38") (pinfunction "IO_L65N_CSO_B_2_38") (pintype "bidirectional"))
      (node (ref "U8") (pin "1") (pinfunction "S#_1") (pintype "input"))
    )
    (net (code "12") (name "FLASH_MISO{slash}BB_SPI_MOSI") (class "Default")
      (node (ref "BBB") (pin "P9.30") (pinfunction "SPI1_D1/MCASP0_AXR0/EHRPWM0_TRIPZONE_P9.30") (pintype "bidirectional"))
      (node (ref "U4") (pin "65") (pinfunction "IO_L3P_D0_DIN_MISO_MISO1_2_65") (pintype "bidirectional"))
      (node (ref "U8") (pin "2") (pinfunction "DQ1_2") (pintype "output"))
    )
    (net (code "13") (name "FLASH_MOSI") (class "Default")
      (node (ref "U4") (pin "64") (pinfunction "IO_L3N_MOSI_CSI_B_MISO0_2_64") (pintype "bidirectional"))
      (node (ref "U8") (pin "5") (pinfunction "DQ0_5") (pintype "input"))
    )
    (net (code "14") (name "FLASH_RESET") (class "Default")
      (node (ref "JP6") (pin "1") (pinfunction "1_1") (pintype "passive"))
      (node (ref "R29") (pin "2") (pinfunction "2_2") (pintype "passive"))
      (node (ref "U3") (pin "12") (pinfunction "IO7_12") (pintype "bidirectional"))
      (node (ref "U8") (pin "7") (pinfunction "RESET#_7") (pintype "input"))
    )
    (net (code "15") (name "FPGA_DONE") (class "Default")
      (node (ref "R13") (pin "2") (pinfunction "2_2") (pintype "passive"))
      (node (ref "U3") (pin "7") (pinfunction "IO3_7") (pintype "bidirectional"))
      (node (ref "U4") (pin "71") (pinfunction "DONE_2_71") (pintype "bidirectional"))
    )
    (net (code "16") (name "FPGA_INIT_B") (class "Default")
      (node (ref "R26") (pin "2") (pinfunction "2_2") (pintype "passive"))
      (node (ref "U3") (pin "6") (pinfunction "IO2_6") (pintype "bidirectional"))
      (node (ref "U4") (pin "39") (pinfunction "IO_L65P_INIT_B_2_39") (pintype "bidirectional"))
    )
    (net (code "17") (name "FPGA_MODE0") (class "Default")
      (node (ref "JP3") (pin "2") (pinfunction "2_2") (pintype "passive"))
      (node (ref "R14") (pin "1") (pinfunction "1_1") (pintype "passive"))
      (node (ref "U3") (pin "4") (pinfunction "IO0_4") (pintype "bidirectional"))
      (node (ref "U4") (pin "69") (pinfunction "IO_L1N_M0_CMPMISO_2_69") (pintype "bidirectional"))
    )
    (net (code "18") (name "FPGA_MODE1") (class "Default")
      (node (ref "JP4") (pin "2") (pinfunction "2_2") (pintype "passive"))
      (node (ref "R15") (pin "1") (pinfunction "1_1") (pintype "passive"))
      (node (ref "U3") (pin "5") (pinfunction "IO1_5") (pintype "bidirectional"))
      (node (ref "U4") (pin "60") (pinfunction "IO_L13P_M1_2_60") (pintype "bidirectional"))
    )
    (net (code "19") (name "FPGA_PROGRAM") (class "Default")
      (node (ref "R27") (pin "1") (pinfunction "1_1") (pintype "passive"))
      (node (ref "U3") (pin "10") (pinfunction "IO5_10") (pintype "bidirectional"))
      (node (ref "U4") (pin "37") (pinfunction "PROGRAM_B_2_37") (pintype "bidirectional"))
    )
    (net (code "20") (name "GND") (class "Default")
      (node (ref "BBB") (pin "P8.1") (pinfunction "GND_P8.1") (pintype "power_in"))
      (node (ref "BBB") (pin "P8.2") (pinfunction "GND_P8.2") (pintype "power_in"))
      (node (ref "BBB") (pin "P9.1") (pinfunction "DGND_P9.1") (pintype "power_in"))
      (node (ref "BBB") (pin "P9.2") (pinfunction "DGND_P9.2") (pintype "power_in"))
      (node (ref "BBB") (pin "P9.43") (pinfunction "DGND_P9.43") (pintype "bidirectional"))
      (node (ref "BBB") (pin "P9.44") (pinfunction "DGND_P9.44") (pintype "bidirectional"))
      (node (ref "BBB") (pin "P9.45") (pinfunction "DGND_P9.45") (pintype "bidirectional"))
      (node (ref "BBB") (pin "P9.46") (pinfunction "DGND_P9.46") (pintype "bidirectional"))
      (node (ref "C1") (pin "1") (pinfunction "1_1") (pintype "passive"))
      (node (ref "C10") (pin "2") (pinfunction "2_2") (pintype "passive"))
      (node (ref "C11") (pin "2") (pinfunction "2_2") (pintype "passive"))
      (node (ref "C12") (pin "2") (pinfunction "2_2") (pintype "passive"))
      (node (ref "C13") (pin "2") (pinfunction "2_2") (pintype "passive"))
      (node (ref "C15") (pin "2") (pinfunction "2_2") (pintype "passive"))
      (node (ref "C16") (pin "2") (pinfunction "2_2") (pintype "passive"))
      (node (ref "C19") (pin "2") (pinfunction "2_2") (pintype "passive"))
      (node (ref "C2") (pin "1") (pinfunction "1_1") (pintype "passive"))
      (node (ref "C21") (pin "2") (pinfunction "2_2") (pintype "passive"))
      (node (ref "C22") (pin "2") (pinfunction "2_2") (pintype "passive"))
      (node (ref "C23") (pin "2") (pinfunction "2_2") (pintype "passive"))
      (node (ref "C24") (pin "2") (pinfunction "2_2") (pintype "passive"))
      (node (ref "C26") (pin "2") (pinfunction "2_2") (pintype "passive"))
      (node (ref "C27") (pin "2") (pinfunction "2_2") (pintype "passive"))
      (node (ref "C28") (pin "2") (pinfunction "2_2") (pintype "passive"))
      (node (ref "C29") (pin "2") (pinfunction "2_2") (pintype "passive"))
      (node (ref "C3") (pin "1") (pinfunction "1_1") (pintype "passive"))
      (node (ref "C30") (pin "1") (pinfunction "1_1") (pintype "passive"))
      (node (ref "C31") (pin "2") (pinfunction "2_2") (pintype "passive"))
      (node (ref "C32") (pin "2") (pinfunction "2_2") (pintype "passive"))
      (node (ref "C33") (pin "2") (pinfunction "2_2") (pintype "passive"))
      (node (ref "C34") (pin "2") (pinfunction "2_2") (pintype "passive"))
      (node (ref "C35") (pin "2") (pinfunction "2_2") (pintype "passive"))
      (node (ref "C36") (pin "2") (pinfunction "2_2") (pintype "passive"))
      (node (ref "C37") (pin "2") (pinfunction "2_2") (pintype "passive"))
      (node (ref "C38") (pin "2") (pinfunction "2_2") (pintype "passive"))
      (node (ref "C39") (pin "1") (pinfunction "1_1") (pintype "passive"))
      (node (ref "C4") (pin "1") (pinfunction "1_1") (pintype "passive"))
      (node (ref "C5") (pin "2") (pinfunction "2_2") (pintype "passive"))
      (node (ref "C6") (pin "2") (pinfunction "2_2") (pintype "passive"))
      (node (ref "C7") (pin "2") (pinfunction "2_2") (pintype "passive"))
      (node (ref "C8") (pin "2") (pinfunction "2_2") (pintype "passive"))
      (node (ref "C9") (pin "2") (pinfunction "2_2") (pintype "passive"))
      (node (ref "D4") (pin "C") (pinfunction "C_C") (pintype "passive"))
      (node (ref "DC1") (pin "C") (pinfunction "C_C") (pintype "passive"))
      (node (ref "J1") (pin "2") (pinfunction "2_2") (pintype "passive"))
      (node (ref "J3") (pin "2") (pinfunction "2_2") (pintype "passive"))
      (node (ref "JP3") (pin "1") (pinfunction "1_1") (pintype "passive"))
      (node (ref "JP4") (pin "1") (pinfunction "1_1") (pintype "passive"))
      (node (ref "P3") (pin "3") (pinfunction "3_3") (pintype "passive"))
      (node (ref "PMOD1") (pin "11") (pinfunction "GND_11") (pintype "bidirectional"))
      (node (ref "PMOD1") (pin "5") (pinfunction "GND_5") (pintype "power_in"))
      (node (ref "PMOD2") (pin "11") (pinfunction "GND_11") (pintype "bidirectional"))
      (node (ref "PMOD2") (pin "5") (pinfunction "GND_5") (pintype "power_in"))
      (node (ref "R1") (pin "2") (pinfunction "2_2") (pintype "passive"))
      (node (ref "R100") (pin "1") (pinfunction "1_1") (pintype "passive"))
      (node (ref "R101") (pin "2") (pinfunction "2_2") (pintype "passive"))
      (node (ref "R12") (pin "1") (pinfunction "1_1") (pintype "passive"))
      (node (ref "R29") (pin "1") (pinfunction "1_1") (pintype "passive"))
      (node (ref "R3") (pin "2") (pinfunction "2_2") (pintype "passive"))
      (node (ref "R4") (pin "1") (pinfunction "1_1") (pintype "passive"))
      (node (ref "R5") (pin "1") (pinfunction "1_1") (pintype "passive"))
      (node (ref "U1") (pin "1") (pinfunction "GND_1") (pintype "power_in"))
      (node (ref "U2") (pin "1") (pinfunction "GND_1") (pintype "power_in"))
      (node (ref "U3") (pin "8") (pinfunction "VSS_8") (pintype "power_in"))
      (node (ref "U4") (pin "108") (pinfunction "GND_108") (pintype "power_in"))
      (node (ref "U4") (pin "113") (pinfunction "GND_113") (pintype "power_in"))
      (node (ref "U4") (pin "13") (pinfunction "GND_13") (pintype "power_in"))
      (node (ref "U4") (pin "130") (pinfunction "GND_130") (pintype "power_in"))
      (node (ref "U4") (pin "136") (pinfunction "GND_136") (pintype "power_in"))
      (node (ref "U4") (pin "25") (pinfunction "GND_25") (pintype "power_in"))
      (node (ref "U4") (pin "3") (pinfunction "GND_3") (pintype "power_in"))
      (node (ref "U4") (pin "49") (pinfunction "GND_49") (pintype "power_in"))
      (node (ref "U4") (pin "54") (pinfunction "GND_54") (pintype "power_in"))
      (node (ref "U4") (pin "68") (pinfunction "GND_68") (pintype "power_in"))
      (node (ref "U4") (pin "77") (pinfunction "GND_77") (pintype "power_in"))
      (node (ref "U4") (pin "91") (pinfunction "GND_91") (pintype "power_in"))
      (node (ref "U4") (pin "96") (pinfunction "GND_96") (pintype "power_in"))
      (node (ref "U5") (pin "2") (pinfunction "GND_2") (pintype "power_in"))
      (node (ref "U7") (pin "4") (pinfunction "GND_4") (pintype "power_in"))
      (node (ref "U8") (pin "4") (pinfunction "VSS_4") (pintype "power_in"))
    )
    (net (code "21") (name "GPMC_AD0") (class "Default")
      (node (ref "BBB") (pin "P8.25") (pinfunction "GPIO1_0/GPMC_AD0/MMC1_DAT0_P8.25") (pintype "bidirectional"))
      (node (ref "U4") (pin "97") (pinfunction "IO_L34N_1_97") (pintype "bidirectional"))
    )
    (net (code "22") (name "GPMC_AD1") (class "Default")
      (node (ref "BBB") (pin "P8.24") (pinfunction "GPIO1_1/GPMC_AD1/MMC1_DAT1_P8.24") (pintype "bidirectional"))
      (node (ref "U4") (pin "98") (pinfunction "IO_L34P_1_98") (pintype "bidirectional"))
    )
    (net (code "23") (name "GPMC_AD2") (class "Default")
      (node (ref "BBB") (pin "P8.5") (pinfunction "GPIO1_2/GPMC_AD2/MMC1_DAT2_P8.5") (pintype "bidirectional"))
      (node (ref "U4") (pin "121") (pinfunction "IO_L62P_0_121") (pintype "bidirectional"))
    )
    (net (code "24") (name "GPMC_AD3") (class "Default")
      (node (ref "BBB") (pin "P8.6") (pinfunction "GPIO1_3/GPMC_AD3/MMC1_DAT3_P8.6") (pintype "bidirectional"))
      (node (ref "U4") (pin "120") (pinfunction "IO_L62N_VREF_0_120") (pintype "bidirectional"))
    )
    (net (code "25") (name "GPMC_AD4") (class "Default")
      (node (ref "BBB") (pin "P8.23") (pinfunction "GPIO1_4/GPMC_AD4/MMC1_DAT4_P8.23") (pintype "bidirectional"))
      (node (ref "U4") (pin "99") (pinfunction "IO_L33N_1_99") (pintype "bidirectional"))
    )
    (net (code "26") (name "GPMC_AD5") (class "Default")
      (node (ref "BBB") (pin "P8.22") (pinfunction "GPIO1_5/GPMC_AD5/MMC1_DAT5_P8.22") (pintype "bidirectional"))
      (node (ref "U4") (pin "100") (pinfunction "IO_L33P_1_100") (pintype "bidirectional"))
    )
    (net (code "27") (name "GPMC_AD6") (class "Default")
      (node (ref "BBB") (pin "P8.3") (pinfunction "GPIO1_6/GPMC_AD6/MMC1_DAT6_P8.3") (pintype "bidirectional"))
      (node (ref "U4") (pin "124") (pinfunction "IO_L37P-GCLK13_0_124") (pintype "bidirectional"))
    )
    (net (code "28") (name "GPMC_AD7") (class "Default")
      (node (ref "BBB") (pin "P8.4") (pinfunction "GPIO1_7/GPMC_AD7/MMC1_DAT7_P8.4") (pintype "bidirectional"))
      (node (ref "U4") (pin "123") (pinfunction "IO_L37N_GCLK12_0_123") (pintype "bidirectional"))
    )
    (net (code "29") (name "GPMC_AD8") (class "Default")
      (node (ref "BBB") (pin "P8.19") (pinfunction "EHRPWM2A/GPMC_AD8/LCD_DATA23/MMC1_DAT0/MMC2_DAT4_P8.19") (pintype "bidirectional"))
      (node (ref "U4") (pin "102") (pinfunction "IO_L32P_1_102") (pintype "bidirectional"))
    )
    (net (code "30") (name "GPMC_AD9") (class "Default")
      (node (ref "BBB") (pin "P8.13") (pinfunction "EHRPWM2B/GMPC_AD9/LCD_DATA22/MMC1_DAT1/MMC2_DAT5_P8.13") (pintype "bidirectional"))
      (node (ref "U4") (pin "105") (pinfunction "IO_L1P_1_105") (pintype "bidirectional"))
    )
    (net (code "31") (name "GPMC_AD10") (class "Default")
      (node (ref "BBB") (pin "P8.14") (pinfunction "BPIO0_26/GPMC_AD10/LCD_DATA21/MMC1_DAT2/MMC2_DAT6_P8.14") (pintype "bidirectional"))
      (node (ref "U4") (pin "104") (pinfunction "IO_L1N_VREF_1_104") (pintype "bidirectional"))
    )
    (net (code "32") (name "GPMC_AD11") (class "Default")
      (node (ref "BBB") (pin "P8.17") (pinfunction "GPIO0_27/GPMC_AD11/LCD_DATA20/MMC1_DAT3/MMC2_DAT7_P8.17") (pintype "bidirectional"))
      (node (ref "U4") (pin "94") (pinfunction "IO_L40N_GCLK10_1_94") (pintype "bidirectional"))
    )
    (net (code "33") (name "GPMC_AD12") (class "Default")
      (node (ref "BBB") (pin "P8.12") (pinfunction "GPIO1_12/GPMC_AD12/LCD_DATA19/MMC1_DAT4/MMC2_DAT0_P8.12") (pintype "bidirectional"))
      (node (ref "U4") (pin "114") (pinfunction "IO_L65N_SCP2_0_114") (pintype "bidirectional"))
    )
    (net (code "34") (name "GPMC_AD13") (class "Default")
      (node (ref "BBB") (pin "P8.11") (pinfunction "GPIO1_13/GPMC_AD13/LCD_DATA18/MMC1_DAT5/MMC2_DAT1_P8.11") (pintype "bidirectional"))
      (node (ref "U4") (pin "115") (pinfunction "IO_L65P_SCP3_0_115") (pintype "bidirectional"))
    )
    (net (code "35") (name "GPMC_AD14") (class "Default")
      (node (ref "BBB") (pin "P8.16") (pinfunction "GPIO1_14/GPMC_AD14/LCD_DATA17/MMC1_DAT6/MMC2_DAT2_P8.16") (pintype "bidirectional"))
      (node (ref "U4") (pin "93") (pinfunction "IO_L41P_GCLK9_IRDY1_1_93") (pintype "bidirectional"))
    )
    (net (code "36") (name "GPMC_AD15") (class "Default")
      (node (ref "BBB") (pin "P8.15") (pinfunction "GPIO1_15/GPMC_AD15/LCD_DATA16/MMC1_DAT7/MMC2_DAT3_P8.15") (pintype "bidirectional"))
      (node (ref "U4") (pin "92") (pinfunction "IO_L41N_GCLK8_1_92") (pintype "bidirectional"))
    )
    (net (code "37") (name "GPMC_ADVN") (class "Default")
      (node (ref "BBB") (pin "P8.7") (pinfunction "TIMER4/GPMC_ADVN_ALE_P8.7") (pintype "bidirectional"))
      (node (ref "U4") (pin "119") (pinfunction "IO_L63P_SCP7_0_119") (pintype "bidirectional"))
    )
    (net (code "38") (name "GPMC_BE0N") (class "Default")
      (node (ref "BBB") (pin "P8.9") (pinfunction "TIMER5/GPMC_BE0N_CLE_P8.9") (pintype "bidirectional"))
      (node (ref "U4") (pin "117") (pinfunction "IO_L64P_SCP5_0_117") (pintype "bidirectional"))
    )
    (net (code "39") (name "GPMC_BE1N") (class "Default")
      (node (ref "BBB") (pin "P9.12") (pinfunction "GPIO1_28/GPMC_BE1N/MII2_COL/GPMC_CSN6_P9.12") (pintype "bidirectional"))
      (node (ref "U4") (pin "88") (pinfunction "IO_L42P_GCLK7_1_88") (pintype "bidirectional"))
    )
    (net (code "40") (name "GPMC_CLK") (class "Default")
      (node (ref "BBB") (pin "P8.18") (pinfunction "GPIO2_1/GPMC_CLK_MUX0/LCD_MEMORY_CLK/GPMC_WAIT1/MMC2_CLK_P8.18") (pintype "bidirectional"))
      (node (ref "U4") (pin "95") (pinfunction "IO_L40P_GCLK11_1_95") (pintype "bidirectional"))
    )
    (net (code "41") (name "GPMC_CSN1") (class "Default")
      (node (ref "BBB") (pin "P8.21") (pinfunction "GPIO1_30/GPMC_CSN1/GPMC_CLK/MMC1_CLK_P8.21") (pintype "bidirectional"))
      (node (ref "U4") (pin "101") (pinfunction "IO_L32N_1_101") (pintype "bidirectional"))
    )
    (net (code "42") (name "GPMC_OEN") (class "Default")
      (node (ref "BBB") (pin "P8.8") (pinfunction "TIMER7/GPMC_OEN_REN_P8.8") (pintype "bidirectional"))
      (node (ref "U4") (pin "118") (pinfunction "IO_L63N_SCP6_0_118") (pintype "bidirectional"))
    )
    (net (code "43") (name "GPMC_WE1N") (class "Default")
      (node (ref "BBB") (pin "P8.10") (pinfunction "TIMER6/GPMC_WEN_P8.10") (pintype "bidirectional"))
      (node (ref "U4") (pin "116") (pinfunction "IO_L64N_SCP4_0_116") (pintype "bidirectional"))
    )
    (net (code "44") (name "Net-(D2-PadA)") (class "Default")
      (node (ref "D2") (pin "A") (pinfunction "A_A") (pintype "passive"))
      (node (ref "J1") (pin "1") (pinfunction "1_1") (pintype "passive"))
    )
    (net (code "45") (name "Net-(D4-PadA)") (class "Default")
      (node (ref "D4") (pin "A") (pinfunction "A_A") (pintype "passive"))
      (node (ref "R13") (pin "1") (pinfunction "1_1") (pintype "passive"))
    )
    (net (code "46") (name "Net-(DC1-PadA)") (class "Default")
      (node (ref "DC1") (pin "A") (pinfunction "A_A") (pintype "passive"))
      (node (ref "R2") (pin "1") (pinfunction "1_1") (pintype "passive"))
    )
    (net (code "47") (name "Net-(J3-Pad3)") (class "Default")
      (node (ref "J3") (pin "3") (pinfunction "3_3") (pintype "passive"))
      (node (ref "R10") (pin "1") (pinfunction "1_1") (pintype "passive"))
    )
    (net (code "48") (name "Net-(J3-Pad4)") (class "Default")
      (node (ref "J3") (pin "4") (pinfunction "4_4") (pintype "passive"))
      (node (ref "R6") (pin "1") (pinfunction "1_1") (pintype "passive"))
    )
    (net (code "49") (name "Net-(J3-Pad5)") (class "Default")
      (node (ref "J3") (pin "5") (pinfunction "5_5") (pintype "passive"))
      (node (ref "R7") (pin "1") (pinfunction "1_1") (pintype "passive"))
    )
    (net (code "50") (name "Net-(J3-Pad6)") (class "Default")
      (node (ref "J3") (pin "6") (pinfunction "6_6") (pintype "passive"))
      (node (ref "R9") (pin "1") (pinfunction "1_1") (pintype "passive"))
    )
    (net (code "51") (name "Net-(U3-A0)") (class "Default")
      (node (ref "JP7") (pin "1") (pinfunction "1_1") (pintype "passive"))
      (node (ref "R1") (pin "1") (pinfunction "1_1") (pintype "passive"))
      (node (ref "U3") (pin "1") (pinfunction "A0_1") (pintype "input"))
    )
    (net (code "52") (name "Net-(U3-A1)") (class "Default")
      (node (ref "JP5") (pin "1") (pinfunction "1_1") (pintype "passive"))
      (node (ref "R3") (pin "1") (pinfunction "1_1") (pintype "passive"))
      (node (ref "U3") (pin "2") (pinfunction "A1_2") (pintype "input"))
    )
    (net (code "53") (name "Net-(U3-A2)") (class "Default")
      (node (ref "JP2") (pin "1") (pinfunction "1_1") (pintype "passive"))
      (node (ref "R101") (pin "1") (pinfunction "1_1") (pintype "passive"))
      (node (ref "U3") (pin "3") (pinfunction "A2_3") (pintype "input"))
    )
    (net (code "54") (name "Net-(U4B-IO_L43P_GCLK5_1)") (class "Default")
      (node (ref "U4") (pin "85") (pinfunction "IO_L43P_GCLK5_1_85") (pintype "bidirectional"))
      (node (ref "U5") (pin "3") (pinfunction "OUTPUT_3") (pintype "bidirectional"))
    )
    (net (code "55") (name "Net-(U4E-SUSPEND)") (class "Default")
      (node (ref "R12") (pin "2") (pinfunction "2_2") (pintype "passive"))
      (node (ref "U4") (pin "73") (pinfunction "SUSPEND_73") (pintype "bidirectional"))
    )
    (net (code "56") (name "Net-(U7-A0)") (class "Default")
      (node (ref "R4") (pin "2") (pinfunction "2_2") (pintype "passive"))
      (node (ref "SJ1") (pin "2") (pinfunction "2_2") (pintype "passive"))
      (node (ref "U7") (pin "1") (pinfunction "A0_1") (pintype "input"))
    )
    (net (code "57") (name "Net-(U7-A1)") (class "Default")
      (node (ref "R5") (pin "2") (pinfunction "2_2") (pintype "passive"))
      (node (ref "SJ2") (pin "2") (pinfunction "2_2") (pintype "passive"))
      (node (ref "U7") (pin "2") (pinfunction "A1_2") (pintype "input"))
    )
    (net (code "58") (name "Net-(U7-A2)") (class "Default")
      (node (ref "R100") (pin "2") (pinfunction "2_2") (pintype "passive"))
      (node (ref "SJ3") (pin "2") (pinfunction "2_2") (pintype "passive"))
      (node (ref "U7") (pin "3") (pinfunction "A2_3") (pintype "input"))
    )
    (net (code "59") (name "PMOD1_1") (class "Default")
      (node (ref "PMOD1") (pin "1") (pinfunction "IO1_1") (pintype "bidirectional"))
      (node (ref "U4") (pin "112") (pinfunction "IO_L66P_SCP1_0_112") (pintype "bidirectional"))
    )
    (net (code "60") (name "PMOD1_2") (class "Default")
      (node (ref "PMOD1") (pin "2") (pinfunction "IO2_2") (pintype "bidirectional"))
      (node (ref "U4") (pin "111") (pinfunction "IO_L66N_SCP0_0_111") (pintype "bidirectional"))
    )
    (net (code "61") (name "PMOD1_3") (class "Default")
      (node (ref "PMOD1") (pin "3") (pinfunction "IO3_3") (pintype "input"))
      (node (ref "U4") (pin "67") (pinfunction "IO_L2P_CPMCLK_2_67") (pintype "bidirectional"))
    )
    (net (code "62") (name "PMOD1_4") (class "Default")
      (node (ref "PMOD1") (pin "4") (pinfunction "IO4_4") (pintype "bidirectional"))
      (node (ref "U4") (pin "66") (pinfunction "IO_L2N_CMPMOSI_2_66") (pintype "bidirectional"))
    )
    (net (code "63") (name "PMOD1_7") (class "Default")
      (node (ref "PMOD1") (pin "7") (pinfunction "IO5_7") (pintype "bidirectional"))
      (node (ref "U4") (pin "62") (pinfunction "IO_L12P_D1_MISO2_2_62") (pintype "bidirectional"))
    )
    (net (code "64") (name "PMOD1_8") (class "Default")
      (node (ref "PMOD1") (pin "8") (pinfunction "IO6_8") (pintype "bidirectional"))
      (node (ref "U4") (pin "61") (pinfunction "IO_L12N_D2_MISO3_2_61") (pintype "bidirectional"))
    )
    (net (code "65") (name "PMOD1_9") (class "Default")
      (node (ref "PMOD1") (pin "9") (pinfunction "IO7_9") (pintype "bidirectional"))
      (node (ref "U4") (pin "58") (pinfunction "IO_L14P_D11_2_58") (pintype "bidirectional"))
    )
    (net (code "66") (name "PMOD1_10") (class "Default")
      (node (ref "PMOD1") (pin "10") (pinfunction "IO8_10") (pintype "bidirectional"))
      (node (ref "U4") (pin "57") (pinfunction "IO_L14N-D12_2_57") (pintype "bidirectional"))
    )
    (net (code "67") (name "PMOD2_1") (class "Default")
      (node (ref "PMOD2") (pin "1") (pinfunction "IO1_1") (pintype "bidirectional"))
      (node (ref "U4") (pin "56") (pinfunction "IO_L30P_GCLK1_D13_2_56") (pintype "bidirectional"))
    )
    (net (code "68") (name "PMOD2_2") (class "Default")
      (node (ref "PMOD2") (pin "2") (pinfunction "IO2_2") (pintype "bidirectional"))
      (node (ref "U4") (pin "55") (pinfunction "IO_L30N_GCLK0_USERCCLK_2_55") (pintype "bidirectional"))
    )
    (net (code "69") (name "PMOD2_3") (class "Default")
      (node (ref "PMOD2") (pin "3") (pinfunction "IO3_3") (pintype "input"))
      (node (ref "U4") (pin "48") (pinfunction "IO_L48P_D7_2_48") (pintype "bidirectional"))
    )
    (net (code "70") (name "PMOD2_4") (class "Default")
      (node (ref "PMOD2") (pin "4") (pinfunction "IO4_4") (pintype "bidirectional"))
      (node (ref "U4") (pin "47") (pinfunction "IO_L48N_RDWR_B_VREF_2_47") (pintype "bidirectional"))
    )
    (net (code "71") (name "PMOD2_7") (class "Default")
      (node (ref "PMOD2") (pin "7") (pinfunction "IO5_7") (pintype "bidirectional"))
      (node (ref "U4") (pin "46") (pinfunction "IO_L49P_D3_2_46") (pintype "bidirectional"))
    )
    (net (code "72") (name "PMOD2_8") (class "Default")
      (node (ref "PMOD2") (pin "8") (pinfunction "IO6_8") (pintype "bidirectional"))
      (node (ref "U4") (pin "45") (pinfunction "IO_L49N_D4_2_45") (pintype "bidirectional"))
    )
    (net (code "73") (name "PMOD2_9") (class "Default")
      (node (ref "PMOD2") (pin "9") (pinfunction "IO7_9") (pintype "bidirectional"))
      (node (ref "U4") (pin "44") (pinfunction "IO_L62P_D5_2_44") (pintype "bidirectional"))
    )
    (net (code "74") (name "PMOD2_10") (class "Default")
      (node (ref "PMOD2") (pin "10") (pinfunction "IO8_10") (pintype "bidirectional"))
      (node (ref "U4") (pin "43") (pinfunction "IO_L62N_D6_2_43") (pintype "bidirectional"))
    )
    (net (code "75") (name "TCK") (class "Default")
      (node (ref "R10") (pin "2") (pinfunction "2_2") (pintype "passive"))
      (node (ref "U4") (pin "109") (pinfunction "TCK_109") (pintype "bidirectional"))
    )
    (net (code "76") (name "TDI") (class "Default")
      (node (ref "R7") (pin "2") (pinfunction "2_2") (pintype "passive"))
      (node (ref "U4") (pin "110") (pinfunction "TDI_110") (pintype "bidirectional"))
    )
    (net (code "77") (name "TDO") (class "Default")
      (node (ref "R6") (pin "2") (pinfunction "2_2") (pintype "passive"))
      (node (ref "U4") (pin "106") (pinfunction "TDO_106") (pintype "bidirectional"))
    )
    (net (code "78") (name "TMS") (class "Default")
      (node (ref "R9") (pin "2") (pinfunction "2_2") (pintype "passive"))
      (node (ref "U4") (pin "107") (pinfunction "TMS_107") (pintype "bidirectional"))
    )
    (net (code "79") (name "VIN_5V") (class "Default")
      (node (ref "C1") (pin "2") (pinfunction "2_2") (pintype "passive"))
      (node (ref "D1") (pin "C") (pinfunction "C_C") (pintype "passive"))
      (node (ref "D2") (pin "C") (pinfunction "C_C") (pintype "passive"))
      (node (ref "P3") (pin "1") (pinfunction "1_1") (pintype "passive"))
      (node (ref "U1") (pin "3") (pinfunction "VIN_3") (pintype "power_in"))
    )
    (net (code "80") (name "unconnected-(BBBA-GPIO1_29{slash}GPMC_CSN0-PadP8.26)") (class "Default")
      (node (ref "BBB") (pin "P8.26") (pinfunction "GPIO1_29/GPMC_CSN0_P8.26") (pintype "bidirectional"))
    )
    (net (code "81") (name "unconnected-(BBBA-GPIO1_31{slash}GPMC_CSN2{slash}GPMC_BE1N{slash}MMC1_CMD-PadP8.20)") (class "Default")
      (node (ref "BBB") (pin "P8.20") (pinfunction "GPIO1_31/GPMC_CSN2/GPMC_BE1N/MMC1_CMD_P8.20") (pintype "bidirectional"))
    )
    (net (code "82") (name "unconnected-(BBBA-GPIO2_6{slash}LCD_DATA0{slash}GPMC_A0-PadP8.45)") (class "Default")
      (node (ref "BBB") (pin "P8.45") (pinfunction "GPIO2_6/LCD_DATA0/GPMC_A0_P8.45") (pintype "bidirectional"))
    )
    (net (code "83") (name "unconnected-(BBBA-GPIO2_7{slash}LCD_DATA1{slash}GPMC_A1-PadP8.46)") (class "Default")
      (node (ref "BBB") (pin "P8.46") (pinfunction "GPIO2_7/LCD_DATA1/GPMC_A1_P8.46") (pintype "bidirectional"))
    )
    (net (code "84") (name "unconnected-(BBBA-GPIO2_8{slash}LCD_DATA2{slash}GPMC_A2-PadP8.43)") (class "Default")
      (node (ref "BBB") (pin "P8.43") (pinfunction "GPIO2_8/LCD_DATA2/GPMC_A2_P8.43") (pintype "bidirectional"))
    )
    (net (code "85") (name "unconnected-(BBBA-GPIO2_9{slash}LCD_DATA3{slash}GPMC_A3-PadP8.44)") (class "Default")
      (node (ref "BBB") (pin "P8.44") (pinfunction "GPIO2_9/LCD_DATA3/GPMC_A3_P8.44") (pintype "bidirectional"))
    )
    (net (code "86") (name "unconnected-(BBBA-GPIO2_10{slash}LCD_DATA4{slash}GPMC_A4-PadP8.41)") (class "Default")
      (node (ref "BBB") (pin "P8.41") (pinfunction "GPIO2_10/LCD_DATA4/GPMC_A4_P8.41") (pintype "bidirectional"))
    )
    (net (code "87") (name "unconnected-(BBBA-GPIO2_11{slash}LCD_DATA5{slash}GPMC_A5-PadP8.42)") (class "Default")
      (node (ref "BBB") (pin "P8.42") (pinfunction "GPIO2_11/LCD_DATA5/GPMC_A5_P8.42") (pintype "bidirectional"))
    )
    (net (code "88") (name "unconnected-(BBBA-GPIO2_12{slash}LCD_DATA6{slash}GPMC_A6-PadP8.39)") (class "Default")
      (node (ref "BBB") (pin "P8.39") (pinfunction "GPIO2_12/LCD_DATA6/GPMC_A6_P8.39") (pintype "bidirectional"))
    )
    (net (code "89") (name "unconnected-(BBBA-GPIO2_13{slash}LCD_DATA7{slash}GPMC_A7-PadP8.40)") (class "Default")
      (node (ref "BBB") (pin "P8.40") (pinfunction "GPIO2_13/LCD_DATA7/GPMC_A7_P8.40") (pintype "bidirectional"))
    )
    (net (code "90") (name "unconnected-(BBBA-GPIO2_22{slash}LCD_VSYNC{slash}GPMC_A8-PadP8.27)") (class "Default")
      (node (ref "BBB") (pin "P8.27") (pinfunction "GPIO2_22/LCD_VSYNC/GPMC_A8_P8.27") (pintype "bidirectional"))
    )
    (net (code "91") (name "unconnected-(BBBA-GPIO2_23{slash}LCD_HSYNC{slash}GPMC_A9-PadP8.29)") (class "Default")
      (node (ref "BBB") (pin "P8.29") (pinfunction "GPIO2_23/LCD_HSYNC/GPMC_A9_P8.29") (pintype "bidirectional"))
    )
    (net (code "92") (name "unconnected-(BBBA-GPIO2_24{slash}LCD_PCLK{slash}GPMC_A10-PadP8.28)") (class "Default")
      (node (ref "BBB") (pin "P8.28") (pinfunction "GPIO2_24/LCD_PCLK/GPMC_A10_P8.28") (pintype "bidirectional"))
    )
    (net (code "93") (name "unconnected-(BBBA-GPIO2_25{slash}LCD_AC_BIAS_EN{slash}GPMC_A11-PadP8.30)") (class "Default")
      (node (ref "BBB") (pin "P8.30") (pinfunction "GPIO2_25/LCD_AC_BIAS_EN/GPMC_A11_P8.30") (pintype "bidirectional"))
    )
    (net (code "94") (name "unconnected-(BBBA-UART3_CTSN{slash}LCD_DATA10{slash}GPMC_A14-PadP8.36)") (class "Default")
      (node (ref "BBB") (pin "P8.36") (pinfunction "UART3_CTSN/LCD_DATA10/GPMC_A14_P8.36") (pintype "bidirectional"))
    )
    (net (code "95") (name "unconnected-(BBBA-UART3_RTSN{slash}LCD_DATA11{slash}GPMC_A15-PadP8.34)") (class "Default")
      (node (ref "BBB") (pin "P8.34") (pinfunction "UART3_RTSN/LCD_DATA11/GPMC_A15_P8.34") (pintype "bidirectional"))
    )
    (net (code "96") (name "unconnected-(BBBA-UART4_CTSN{slash}LCD_DATA12{slash}GPMC_A16-PadP8.35)") (class "Default")
      (node (ref "BBB") (pin "P8.35") (pinfunction "UART4_CTSN/LCD_DATA12/GPMC_A16_P8.35") (pintype "bidirectional"))
    )
    (net (code "97") (name "unconnected-(BBBA-UART4_RTSN{slash}LCD_DATA13{slash}GPMC_A17-PadP8.33)") (class "Default")
      (node (ref "BBB") (pin "P8.33") (pinfunction "UART4_RTSN/LCD_DATA13/GPMC_A17_P8.33") (pintype "bidirectional"))
    )
    (net (code "98") (name "unconnected-(BBBA-UART5_CTSN{slash}LCD_DATA14{slash}GPMC_A18-PadP8.31)") (class "Default")
      (node (ref "BBB") (pin "P8.31") (pinfunction "UART5_CTSN/LCD_DATA14/GPMC_A18_P8.31") (pintype "bidirectional"))
    )
    (net (code "99") (name "unconnected-(BBBA-UART5_RTSN{slash}LCD_DATA15{slash}GPMC_A19-PadP8.32)") (class "Default")
      (node (ref "BBB") (pin "P8.32") (pinfunction "UART5_RTSN/LCD_DATA15/GPMC_A19_P8.32") (pintype "bidirectional"))
    )
    (net (code "100") (name "unconnected-(BBBA-UART5_RXD{slash}LCD_DATA9{slash}GPMC_A13-PadP8.38)") (class "Default")
      (node (ref "BBB") (pin "P8.38") (pinfunction "UART5_RXD/LCD_DATA9/GPMC_A13_P8.38") (pintype "bidirectional"))
    )
    (net (code "101") (name "unconnected-(BBBA-UART5_TXD{slash}LCD_DATA8{slash}GPMC_A12-PadP8.37)") (class "Default")
      (node (ref "BBB") (pin "P8.37") (pinfunction "UART5_TXD/LCD_DATA8/GPMC_A12_P8.37") (pintype "bidirectional"))
    )
    (net (code "102") (name "unconnected-(BBBB-AIN0-PadP9.39)") (class "Default")
      (node (ref "BBB") (pin "P9.39") (pinfunction "AIN0_P9.39") (pintype "bidirectional"))
    )
    (net (code "103") (name "unconnected-(BBBB-AIN1-PadP9.40)") (class "Default")
      (node (ref "BBB") (pin "P9.40") (pinfunction "AIN1_P9.40") (pintype "bidirectional"))
    )
    (net (code "104") (name "unconnected-(BBBB-AIN2-PadP9.37)") (class "Default")
      (node (ref "BBB") (pin "P9.37") (pinfunction "AIN2_P9.37") (pintype "bidirectional"))
    )
    (net (code "105") (name "unconnected-(BBBB-AIN3-PadP9.38)") (class "Default")
      (node (ref "BBB") (pin "P9.38") (pinfunction "AIN3_P9.38") (pintype "bidirectional"))
    )
    (net (code "106") (name "unconnected-(BBBB-AIN4-PadP9.33)") (class "Default")
      (node (ref "BBB") (pin "P9.33") (pinfunction "AIN4_P9.33") (pintype "bidirectional"))
    )
    (net (code "107") (name "unconnected-(BBBB-AIN5-PadP9.36)") (class "Default")
      (node (ref "BBB") (pin "P9.36") (pinfunction "AIN5_P9.36") (pintype "bidirectional"))
    )
    (net (code "108") (name "unconnected-(BBBB-AIN6-PadP9.35)") (class "Default")
      (node (ref "BBB") (pin "P9.35") (pinfunction "AIN6_P9.35") (pintype "bidirectional"))
    )
    (net (code "109") (name "unconnected-(BBBB-CLKOUT2-PadP9.41)") (class "Default")
      (node (ref "BBB") (pin "P9.41") (pinfunction "CLKOUT2_P9.41") (pintype "bidirectional"))
    )
    (net (code "110") (name "unconnected-(BBBB-EHRPWM1B{slash}GPMC_A3{slash}MII2_TXD2{slash}RGMII2_TD2-PadP9.16)") (class "Default")
      (node (ref "BBB") (pin "P9.16") (pinfunction "EHRPWM1B/GPMC_A3/MII2_TXD2/RGMII2_TD2_P9.16") (pintype "bidirectional"))
    )
    (net (code "111") (name "unconnected-(BBBB-EHRPWN1A{slash}GPMC_A2{slash}MII2TXD3{slash}RGMII2_TD3-PadP9.14)") (class "Default")
      (node (ref "BBB") (pin "P9.14") (pinfunction "EHRPWN1A/GPMC_A2/MII2TXD3/RGMII2_TD3_P9.14") (pintype "bidirectional"))
    )
    (net (code "112") (name "unconnected-(BBBB-GNDA_ADC-PadP9.34)") (class "Default")
      (node (ref "BBB") (pin "P9.34") (pinfunction "GNDA_ADC_P9.34") (pintype "bidirectional"))
    )
    (net (code "113") (name "unconnected-(BBBB-GPIO0_7-PadP9.42)") (class "Default")
      (node (ref "BBB") (pin "P9.42") (pinfunction "GPIO0_7_P9.42") (pintype "bidirectional"))
    )
    (net (code "114") (name "unconnected-(BBBB-GPIO1_16{slash}GPMC_A0{slash}GMII2_TXEN{slash}RMII2_TCTL-PadP9.15)") (class "Default")
      (node (ref "BBB") (pin "P9.15") (pinfunction "GPIO1_16/GPMC_A0/GMII2_TXEN/RMII2_TCTL_P9.15") (pintype "bidirectional"))
    )
    (net (code "115") (name "unconnected-(BBBB-GPIO1_17{slash}GPMC_A1{slash}GMII2_RXDV{slash}RGMII2_RXDV-PadP9.23)") (class "Default")
      (node (ref "BBB") (pin "P9.23") (pinfunction "GPIO1_17/GPMC_A1/GMII2_RXDV/RGMII2_RXDV_P9.23") (pintype "bidirectional"))
    )
    (net (code "116") (name "unconnected-(BBBB-GPIO3_19{slash}MCASP0_FSR{slash}EQEP0B_IN{slash}MCASP0_AXR3-PadP9.27)") (class "Default")
      (node (ref "BBB") (pin "P9.27") (pinfunction "GPIO3_19/MCASP0_FSR/EQEP0B_IN/MCASP0_AXR3_P9.27") (pintype "bidirectional"))
    )
    (net (code "117") (name "unconnected-(BBBB-HDMI_CLK{slash}GPIO3_21{slash}MCASP0_AHCLKX{slash}EQEP0_STROBE{slash}MCASP0_AXR3-PadP9.25)") (class "Default")
      (node (ref "BBB") (pin "P9.25") (pinfunction "HDMI_CLK/GPIO3_21/MCASP0_AHCLKX/EQEP0_STROBE/MCASP0_AXR3_P9.25") (pintype "bidirectional"))
    )
    (net (code "118") (name "unconnected-(BBBB-I2C1_SCL{slash}SPI0_CS0{slash}MMC2_SDWP{slash}I2C1_SCL-PadP9.17)") (class "Default")
      (node (ref "BBB") (pin "P9.17") (pinfunction "I2C1_SCL/SPI0_CS0/MMC2_SDWP/I2C1_SCL_P9.17") (pintype "bidirectional"))
    )
    (net (code "119") (name "unconnected-(BBBB-I2C1_SDA{slash}SPI0_D1{slash}MMC2_SDWP-PadP9.18)") (class "Default")
      (node (ref "BBB") (pin "P9.18") (pinfunction "I2C1_SDA/SPI0_D1/MMC2_SDWP_P9.18") (pintype "bidirectional"))
    )
    (net (code "120") (name "unconnected-(BBBB-PWR_BUT-PadP9.9)") (class "Default")
      (node (ref "BBB") (pin "P9.9") (pinfunction "PWR_BUT_P9.9") (pintype "bidirectional"))
    )
    (net (code "121") (name "unconnected-(BBBB-SYS_RST-PadP9.10)") (class "Default")
      (node (ref "BBB") (pin "P9.10") (pinfunction "SYS_RST_P9.10") (pintype "bidirectional"))
    )
    (net (code "122") (name "unconnected-(BBBB-UART1_RXD{slash}MMC1_SDWP{slash}DCAN1_TX-PadP9.26)") (class "Default")
      (node (ref "BBB") (pin "P9.26") (pinfunction "UART1_RXD/MMC1_SDWP/DCAN1_TX_P9.26") (pintype "bidirectional"))
    )
    (net (code "123") (name "unconnected-(BBBB-UART1_TXD{slash}UART1_TXD{slash}MMC2_SDWP{slash}DCAN1_RX-PadP9.21)") (class "Default")
      (node (ref "BBB") (pin "P9.21") (pinfunction "UART1_TXD/UART1_TXD/MMC2_SDWP/DCAN1_RX_P9.21") (pintype "bidirectional"))
    )
    (net (code "124") (name "unconnected-(BBBB-UART2_RXD{slash}SPI0_SCLK{slash}UART2_RXD{slash}I2C2_SDA-PadP9.22)") (class "Default")
      (node (ref "BBB") (pin "P9.22") (pinfunction "UART2_RXD/SPI0_SCLK/UART2_RXD/I2C2_SDA_P9.22") (pintype "bidirectional"))
    )
    (net (code "125") (name "unconnected-(BBBB-UART2_TXD{slash}SPI0_D0{slash}UART2_TXD{slash}I2C2_SCL-PadP9.24)") (class "Default")
      (node (ref "BBB") (pin "P9.24") (pinfunction "UART2_TXD/SPI0_D0/UART2_TXD/I2C2_SCL_P9.24") (pintype "bidirectional"))
    )
    (net (code "126") (name "unconnected-(BBBB-UART4_RXD{slash}GPMC_WAIT0{slash}MII2_CRS{slash}GPMC_CSN4-PadP9.11)") (class "Default")
      (node (ref "BBB") (pin "P9.11") (pinfunction "UART4_RXD/GPMC_WAIT0/MII2_CRS/GPMC_CSN4_P9.11") (pintype "bidirectional"))
    )
    (net (code "127") (name "unconnected-(BBBB-UART4_TXD{slash}GPMC_WPM{slash}MII2_RXERR{slash}GPMC_CSN5-PadP9.13)") (class "Default")
      (node (ref "BBB") (pin "P9.13") (pinfunction "UART4_TXD/GPMC_WPM/MII2_RXERR/GPMC_CSN5_P9.13") (pintype "bidirectional"))
    )
    (net (code "128") (name "unconnected-(BBBB-VDD_3V3-PadP9.3)") (class "Default")
      (node (ref "BBB") (pin "P9.3") (pinfunction "VDD_3V3_P9.3") (pintype "bidirectional"))
    )
    (net (code "129") (name "unconnected-(BBBB-VDD_3V3-PadP9.4)") (class "Default")
      (node (ref "BBB") (pin "P9.4") (pinfunction "VDD_3V3_P9.4") (pintype "bidirectional"))
    )
    (net (code "130") (name "unconnected-(BBBB-VDD_5V-PadP9.5)") (class "Default")
      (node (ref "BBB") (pin "P9.5") (pinfunction "VDD_5V_P9.5") (pintype "bidirectional"))
    )
    (net (code "131") (name "unconnected-(BBBB-VDD_5V-PadP9.6)") (class "Default")
      (node (ref "BBB") (pin "P9.6") (pinfunction "VDD_5V_P9.6") (pintype "bidirectional"))
    )
    (net (code "132") (name "unconnected-(BBBB-VDD_ADC-PadP9.32)") (class "Default")
      (node (ref "BBB") (pin "P9.32") (pinfunction "VDD_ADC_P9.32") (pintype "bidirectional"))
    )
    (net (code "133") (name "unconnected-(JP1-Pad1)") (class "Default")
      (node (ref "JP1") (pin "1") (pinfunction "1_1") (pintype "passive"))
    )
    (net (code "134") (name "unconnected-(JP1-Pad2)") (class "Default")
      (node (ref "JP1") (pin "2") (pinfunction "2_2") (pintype "passive"))
    )
    (net (code "135") (name "unconnected-(JP1-Pad3)") (class "Default")
      (node (ref "JP1") (pin "3") (pinfunction "3_3") (pintype "passive"))
    )
    (net (code "136") (name "unconnected-(JP1-Pad4)") (class "Default")
      (node (ref "JP1") (pin "4") (pinfunction "4_4") (pintype "passive"))
    )
    (net (code "137") (name "unconnected-(JP1-Pad5)") (class "Default")
      (node (ref "JP1") (pin "5") (pinfunction "5_5") (pintype "passive"))
    )
    (net (code "138") (name "unconnected-(JP1-Pad6)") (class "Default")
      (node (ref "JP1") (pin "6") (pinfunction "6_6") (pintype "passive"))
    )
    (net (code "139") (name "unconnected-(U3-IO4-Pad9)") (class "Default")
      (node (ref "U3") (pin "9") (pinfunction "IO4_9") (pintype "bidirectional"))
    )
    (net (code "140") (name "unconnected-(U3-~{INT}-Pad13)") (class "Default")
      (node (ref "U3") (pin "13") (pinfunction "~{INT}_13") (pintype "open_collector"))
    )
    (net (code "141") (name "unconnected-(U4A-IO-L1P_HSWAPEN_0-Pad144)") (class "Default")
      (node (ref "U4") (pin "144") (pinfunction "IO-L1P_HSWAPEN_0_144") (pintype "bidirectional"))
    )
    (net (code "142") (name "unconnected-(U4A-IO_L1N_VREF_0-Pad143)") (class "Default")
      (node (ref "U4") (pin "143") (pinfunction "IO_L1N_VREF_0_143") (pintype "bidirectional"))
    )
    (net (code "143") (name "unconnected-(U4A-IO_L2N_0-Pad141)") (class "Default")
      (node (ref "U4") (pin "141") (pinfunction "IO_L2N_0_141") (pintype "bidirectional"))
    )
    (net (code "144") (name "unconnected-(U4A-IO_L2P_0-Pad142)") (class "Default")
      (node (ref "U4") (pin "142") (pinfunction "IO_L2P_0_142") (pintype "bidirectional"))
    )
    (net (code "145") (name "unconnected-(U4A-IO_L3N_0-Pad139)") (class "Default")
      (node (ref "U4") (pin "139") (pinfunction "IO_L3N_0_139") (pintype "bidirectional"))
    )
    (net (code "146") (name "unconnected-(U4A-IO_L3P_0-Pad140)") (class "Default")
      (node (ref "U4") (pin "140") (pinfunction "IO_L3P_0_140") (pintype "bidirectional"))
    )
    (net (code "147") (name "unconnected-(U4A-IO_L4N_0-Pad137)") (class "Default")
      (node (ref "U4") (pin "137") (pinfunction "IO_L4N_0_137") (pintype "bidirectional"))
    )
    (net (code "148") (name "unconnected-(U4A-IO_L4P_0-Pad138)") (class "Default")
      (node (ref "U4") (pin "138") (pinfunction "IO_L4P_0_138") (pintype "bidirectional"))
    )
    (net (code "149") (name "unconnected-(U4A-IO_L34N_GCLK18_0-Pad133)") (class "Default")
      (node (ref "U4") (pin "133") (pinfunction "IO_L34N_GCLK18_0_133") (pintype "bidirectional"))
    )
    (net (code "150") (name "unconnected-(U4A-IO_L34P_GCLK19_0-Pad134)") (class "Default")
      (node (ref "U4") (pin "134") (pinfunction "IO_L34P_GCLK19_0_134") (pintype "bidirectional"))
    )
    (net (code "151") (name "unconnected-(U4A-IO_L35N_GCLK16_0-Pad131)") (class "Default")
      (node (ref "U4") (pin "131") (pinfunction "IO_L35N_GCLK16_0_131") (pintype "bidirectional"))
    )
    (net (code "152") (name "unconnected-(U4A-IO_L35P_GLCK17_0-Pad132)") (class "Default")
      (node (ref "U4") (pin "132") (pinfunction "IO_L35P_GLCK17_0_132") (pintype "bidirectional"))
    )
    (net (code "153") (name "unconnected-(U4A-IO_L36N_GCLK14_0-Pad126)") (class "Default")
      (node (ref "U4") (pin "126") (pinfunction "IO_L36N_GCLK14_0_126") (pintype "bidirectional"))
    )
    (net (code "154") (name "unconnected-(U4A-IO_L36P_GCLK15_0-Pad127)") (class "Default")
      (node (ref "U4") (pin "127") (pinfunction "IO_L36P_GCLK15_0_127") (pintype "bidirectional"))
    )
    (net (code "155") (name "unconnected-(U4B-IO_L42N_GCLK6_TRDY1_1-Pad87)") (class "Default")
      (node (ref "U4") (pin "87") (pinfunction "IO_L42N_GCLK6_TRDY1_1_87") (pintype "bidirectional"))
    )
    (net (code "156") (name "unconnected-(U4B-IO_L43N_GCLK4_1-Pad84)") (class "Default")
      (node (ref "U4") (pin "84") (pinfunction "IO_L43N_GCLK4_1_84") (pintype "bidirectional"))
    )
    (net (code "157") (name "unconnected-(U4B-IO_L45P_1-Pad83)") (class "Default")
      (node (ref "U4") (pin "83") (pinfunction "IO_L45P_1_83") (pintype "bidirectional"))
    )
    (net (code "158") (name "unconnected-(U4B-IO_L46N_1-Pad80)") (class "Default")
      (node (ref "U4") (pin "80") (pinfunction "IO_L46N_1_80") (pintype "bidirectional"))
    )
    (net (code "159") (name "unconnected-(U4B-IO_L47N_1-Pad78)") (class "Default")
      (node (ref "U4") (pin "78") (pinfunction "IO_L47N_1_78") (pintype "bidirectional"))
    )
    (net (code "160") (name "unconnected-(U4B-IO_L47_P1-Pad79)") (class "Default")
      (node (ref "U4") (pin "79") (pinfunction "IO_L47_P1_79") (pintype "bidirectional"))
    )
    (net (code "161") (name "unconnected-(U4B-IO_L74N_DOUT_BUSY_1-Pad74)") (class "Default")
      (node (ref "U4") (pin "74") (pinfunction "IO_L74N_DOUT_BUSY_1_74") (pintype "bidirectional"))
    )
    (net (code "162") (name "unconnected-(U4B-IO_L74P_AWAKE_1-Pad75)") (class "Default")
      (node (ref "U4") (pin "75") (pinfunction "IO_L74P_AWAKE_1_75") (pintype "bidirectional"))
    )
    (net (code "163") (name "unconnected-(U4C-CMPCS_B_2-Pad72)") (class "Default")
      (node (ref "U4") (pin "72") (pinfunction "CMPCS_B_2_72") (pintype "bidirectional"))
    )
    (net (code "164") (name "unconnected-(U4C-IO_L13N_D10_2-Pad59)") (class "Default")
      (node (ref "U4") (pin "59") (pinfunction "IO_L13N_D10_2_59") (pintype "bidirectional"))
    )
    (net (code "165") (name "unconnected-(U4C-IO_L31N_GCLK30_D15_2-Pad50)") (class "Default")
      (node (ref "U4") (pin "50") (pinfunction "IO_L31N_GCLK30_D15_2_50") (pintype "bidirectional"))
    )
    (net (code "166") (name "unconnected-(U4C-IO_L31P_GCLK31_D14_2-Pad51)") (class "Default")
      (node (ref "U4") (pin "51") (pinfunction "IO_L31P_GCLK31_D14_2_51") (pintype "bidirectional"))
    )
    (net (code "167") (name "unconnected-(U4C-IO_L64N_D9_2-Pad40)") (class "Default")
      (node (ref "U4") (pin "40") (pinfunction "IO_L64N_D9_2_40") (pintype "bidirectional"))
    )
    (net (code "168") (name "unconnected-(U4C-IO_L64P_D8_2-Pad41)") (class "Default")
      (node (ref "U4") (pin "41") (pinfunction "IO_L64P_D8_2_41") (pintype "bidirectional"))
    )
    (net (code "169") (name "unconnected-(U4D-IO_L1N_VREF_3-Pad34)") (class "Default")
      (node (ref "U4") (pin "34") (pinfunction "IO_L1N_VREF_3_34") (pintype "bidirectional"))
    )
    (net (code "170") (name "unconnected-(U4D-IO_L1P-3-Pad35)") (class "Default")
      (node (ref "U4") (pin "35") (pinfunction "IO_L1P-3_35") (pintype "bidirectional"))
    )
    (net (code "171") (name "unconnected-(U4D-IO_L2N_3-Pad32)") (class "Default")
      (node (ref "U4") (pin "32") (pinfunction "IO_L2N_3_32") (pintype "bidirectional"))
    )
    (net (code "172") (name "unconnected-(U4D-IO_L2P_3-Pad33)") (class "Default")
      (node (ref "U4") (pin "33") (pinfunction "IO_L2P_3_33") (pintype "bidirectional"))
    )
    (net (code "173") (name "unconnected-(U4D-IO_L36N_3-Pad29)") (class "Default")
      (node (ref "U4") (pin "29") (pinfunction "IO_L36N_3_29") (pintype "bidirectional"))
    )
    (net (code "174") (name "unconnected-(U4D-IO_L36P_3-Pad30)") (class "Default")
      (node (ref "U4") (pin "30") (pinfunction "IO_L36P_3_30") (pintype "bidirectional"))
    )
    (net (code "175") (name "unconnected-(U4D-IO_L37N_3-Pad26)") (class "Default")
      (node (ref "U4") (pin "26") (pinfunction "IO_L37N_3_26") (pintype "bidirectional"))
    )
    (net (code "176") (name "unconnected-(U4D-IO_L37P_3-Pad27)") (class "Default")
      (node (ref "U4") (pin "27") (pinfunction "IO_L37P_3_27") (pintype "bidirectional"))
    )
    (net (code "177") (name "unconnected-(U4D-IO_L41N_GCLK26_3-Pad23)") (class "Default")
      (node (ref "U4") (pin "23") (pinfunction "IO_L41N_GCLK26_3_23") (pintype "bidirectional"))
    )
    (net (code "178") (name "unconnected-(U4D-IO_L41P_GCLK27_3-Pad24)") (class "Default")
      (node (ref "U4") (pin "24") (pinfunction "IO_L41P_GCLK27_3_24") (pintype "bidirectional"))
    )
    (net (code "179") (name "unconnected-(U4D-IO_L42N_GCLK24_3-Pad21)") (class "Default")
      (node (ref "U4") (pin "21") (pinfunction "IO_L42N_GCLK24_3_21") (pintype "bidirectional"))
    )
    (net (code "180") (name "unconnected-(U4D-IO_L42P_GCLK25_TRDY2_3-Pad22)") (class "Default")
      (node (ref "U4") (pin "22") (pinfunction "IO_L42P_GCLK25_TRDY2_3_22") (pintype "bidirectional"))
    )
    (net (code "181") (name "unconnected-(U4D-IO_L43N_GCLK22_IRDY2_3-Pad16)") (class "Default")
      (node (ref "U4") (pin "16") (pinfunction "IO_L43N_GCLK22_IRDY2_3_16") (pintype "bidirectional"))
    )
    (net (code "182") (name "unconnected-(U4D-IO_L43P_GCLK23_3-Pad17)") (class "Default")
      (node (ref "U4") (pin "17") (pinfunction "IO_L43P_GCLK23_3_17") (pintype "bidirectional"))
    )
    (net (code "183") (name "unconnected-(U4D-IO_L44N_GCLK20_3-Pad14)") (class "Default")
      (node (ref "U4") (pin "14") (pinfunction "IO_L44N_GCLK20_3_14") (pintype "bidirectional"))
    )
    (net (code "184") (name "unconnected-(U4D-IO_L44P_GCLK21_3-Pad15)") (class "Default")
      (node (ref "U4") (pin "15") (pinfunction "IO_L44P_GCLK21_3_15") (pintype "bidirectional"))
    )
    (net (code "185") (name "unconnected-(U4D-IO_L49N_3-Pad11)") (class "Default")
      (node (ref "U4") (pin "11") (pinfunction "IO_L49N_3_11") (pintype "bidirectional"))
    )
    (net (code "186") (name "unconnected-(U4D-IO_L49P_3-Pad12)") (class "Default")
      (node (ref "U4") (pin "12") (pinfunction "IO_L49P_3_12") (pintype "bidirectional"))
    )
    (net (code "187") (name "unconnected-(U4D-IO_L50N_3-Pad9)") (class "Default")
      (node (ref "U4") (pin "9") (pinfunction "IO_L50N_3_9") (pintype "bidirectional"))
    )
    (net (code "188") (name "unconnected-(U4D-IO_L50P_3-Pad10)") (class "Default")
      (node (ref "U4") (pin "10") (pinfunction "IO_L50P_3_10") (pintype "bidirectional"))
    )
    (net (code "189") (name "unconnected-(U4D-IO_L51N_3-Pad7)") (class "Default")
      (node (ref "U4") (pin "7") (pinfunction "IO_L51N_3_7") (pintype "bidirectional"))
    )
    (net (code "190") (name "unconnected-(U4D-IO_L51P_3-Pad8)") (class "Default")
      (node (ref "U4") (pin "8") (pinfunction "IO_L51P_3_8") (pintype "bidirectional"))
    )
    (net (code "191") (name "unconnected-(U4D-IO_L52N_3-Pad5)") (class "Default")
      (node (ref "U4") (pin "5") (pinfunction "IO_L52N_3_5") (pintype "bidirectional"))
    )
    (net (code "192") (name "unconnected-(U4D-IO_L52P_3-Pad6)") (class "Default")
      (node (ref "U4") (pin "6") (pinfunction "IO_L52P_3_6") (pintype "bidirectional"))
    )
    (net (code "193") (name "unconnected-(U4D-IO_L83N_VREF_3-Pad1)") (class "Default")
      (node (ref "U4") (pin "1") (pinfunction "IO_L83N_VREF_3_1") (pintype "bidirectional"))
    )
    (net (code "194") (name "unconnected-(U4D-IO_L83P_3-Pad2)") (class "Default")
      (node (ref "U4") (pin "2") (pinfunction "IO_L83P_3_2") (pintype "bidirectional"))
    )
  )
)
